# EEZ_DIB_DCP405_r3B3a.net
KiCad netlist of a schematic drawn in EAGLE
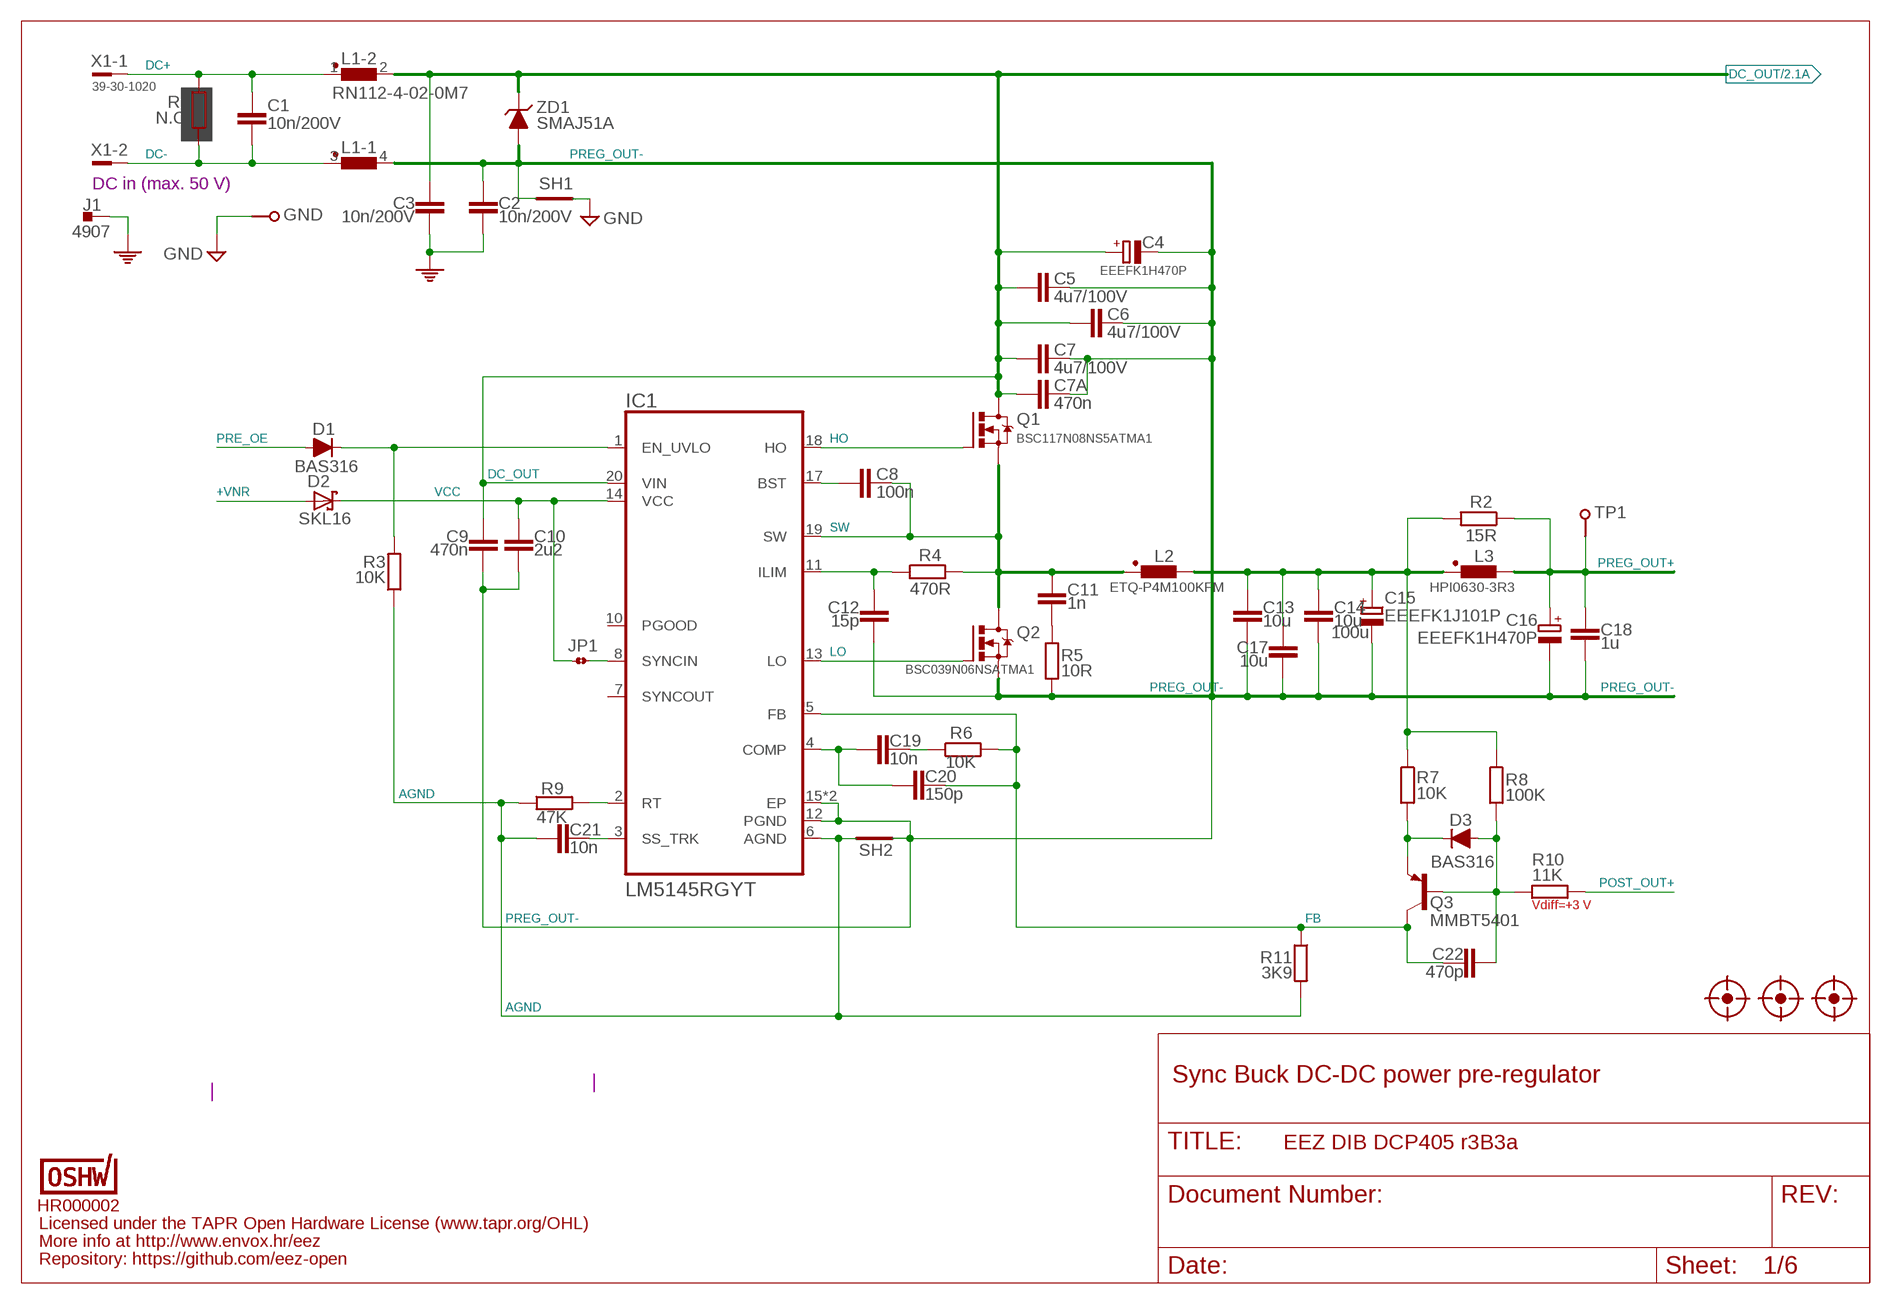
[diagram p0: schematic, sheet 1]
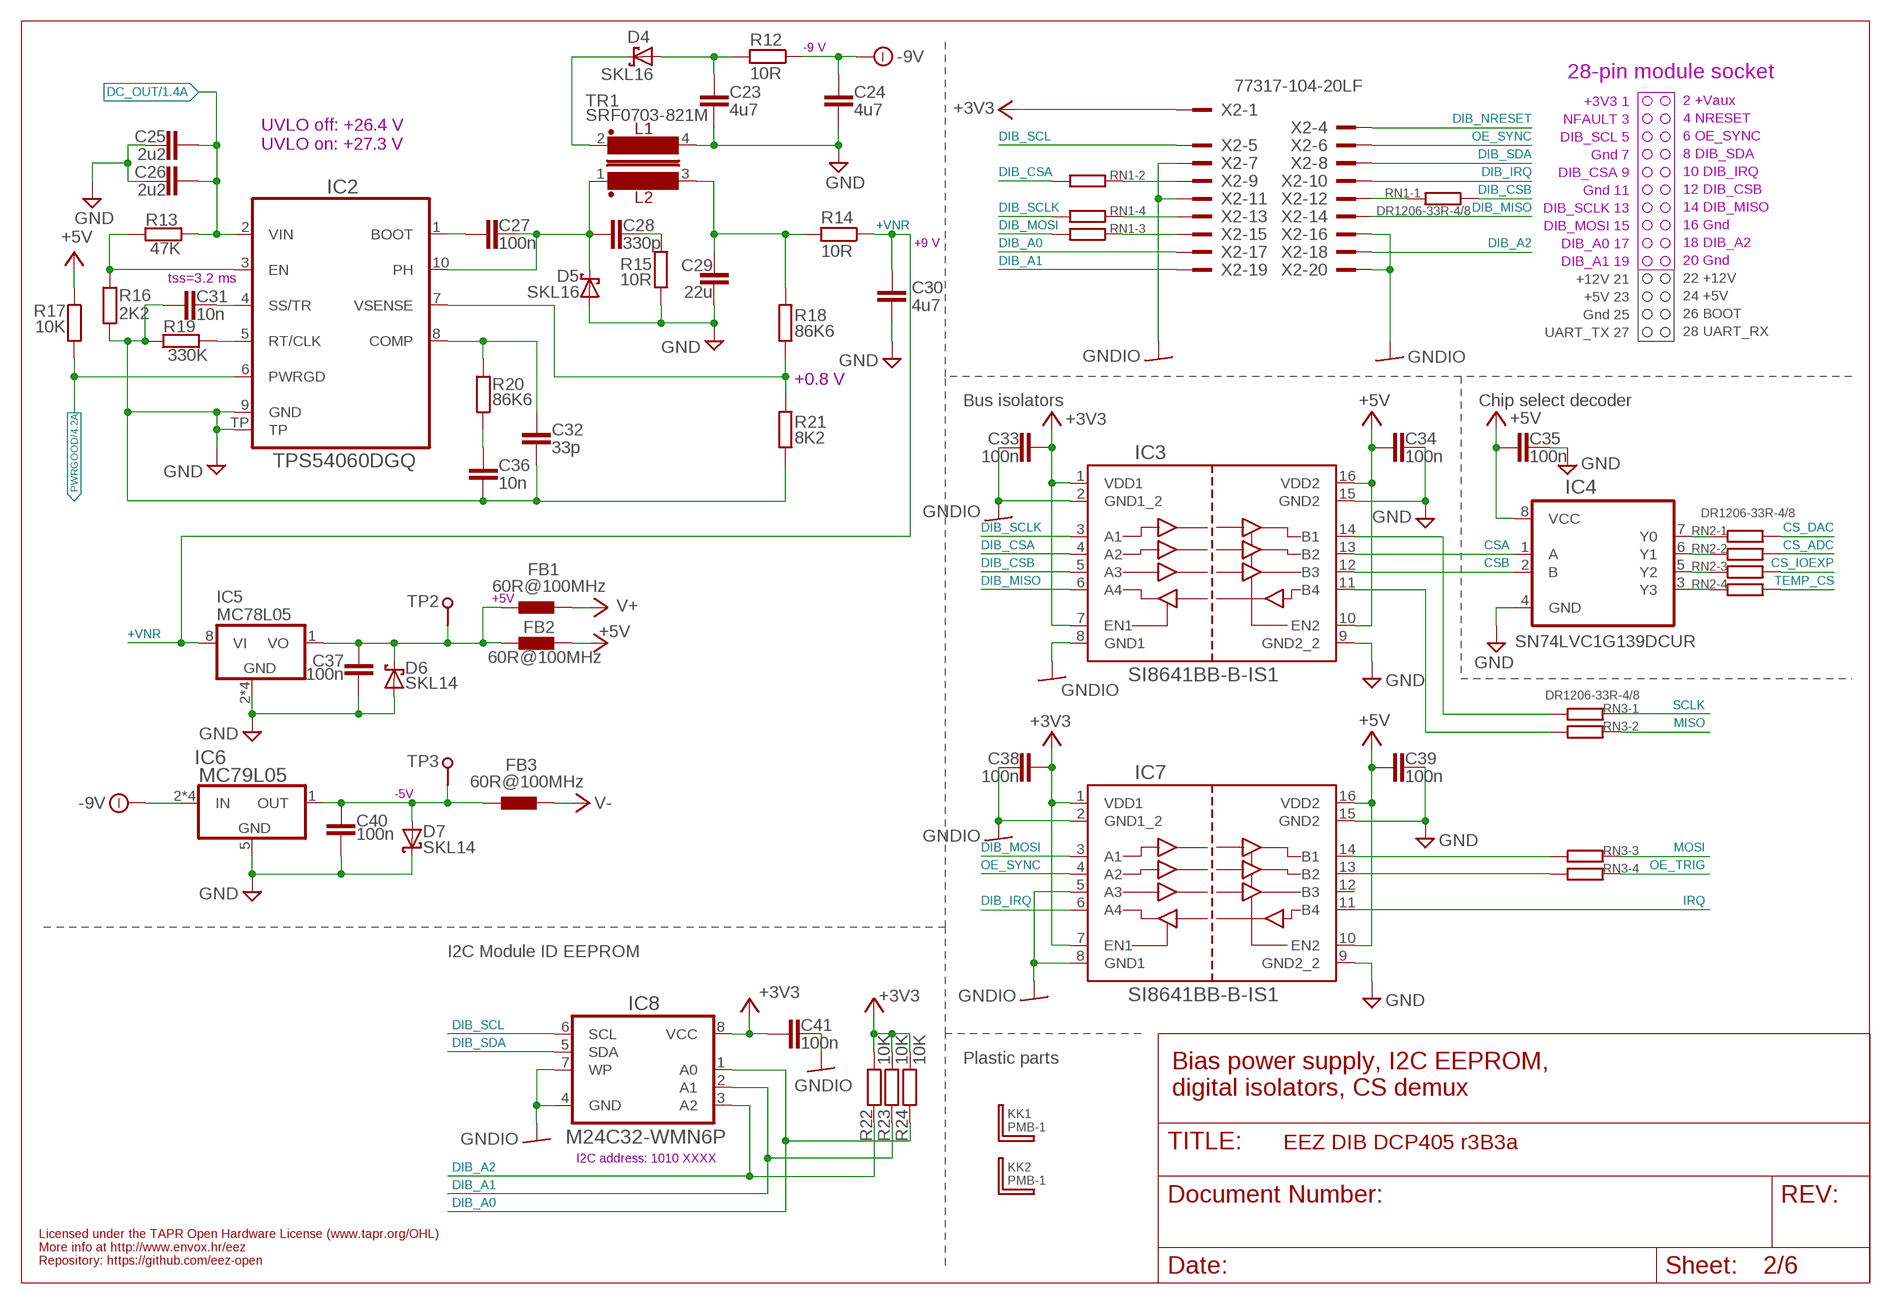
[diagram p1: schematic, sheet 2]
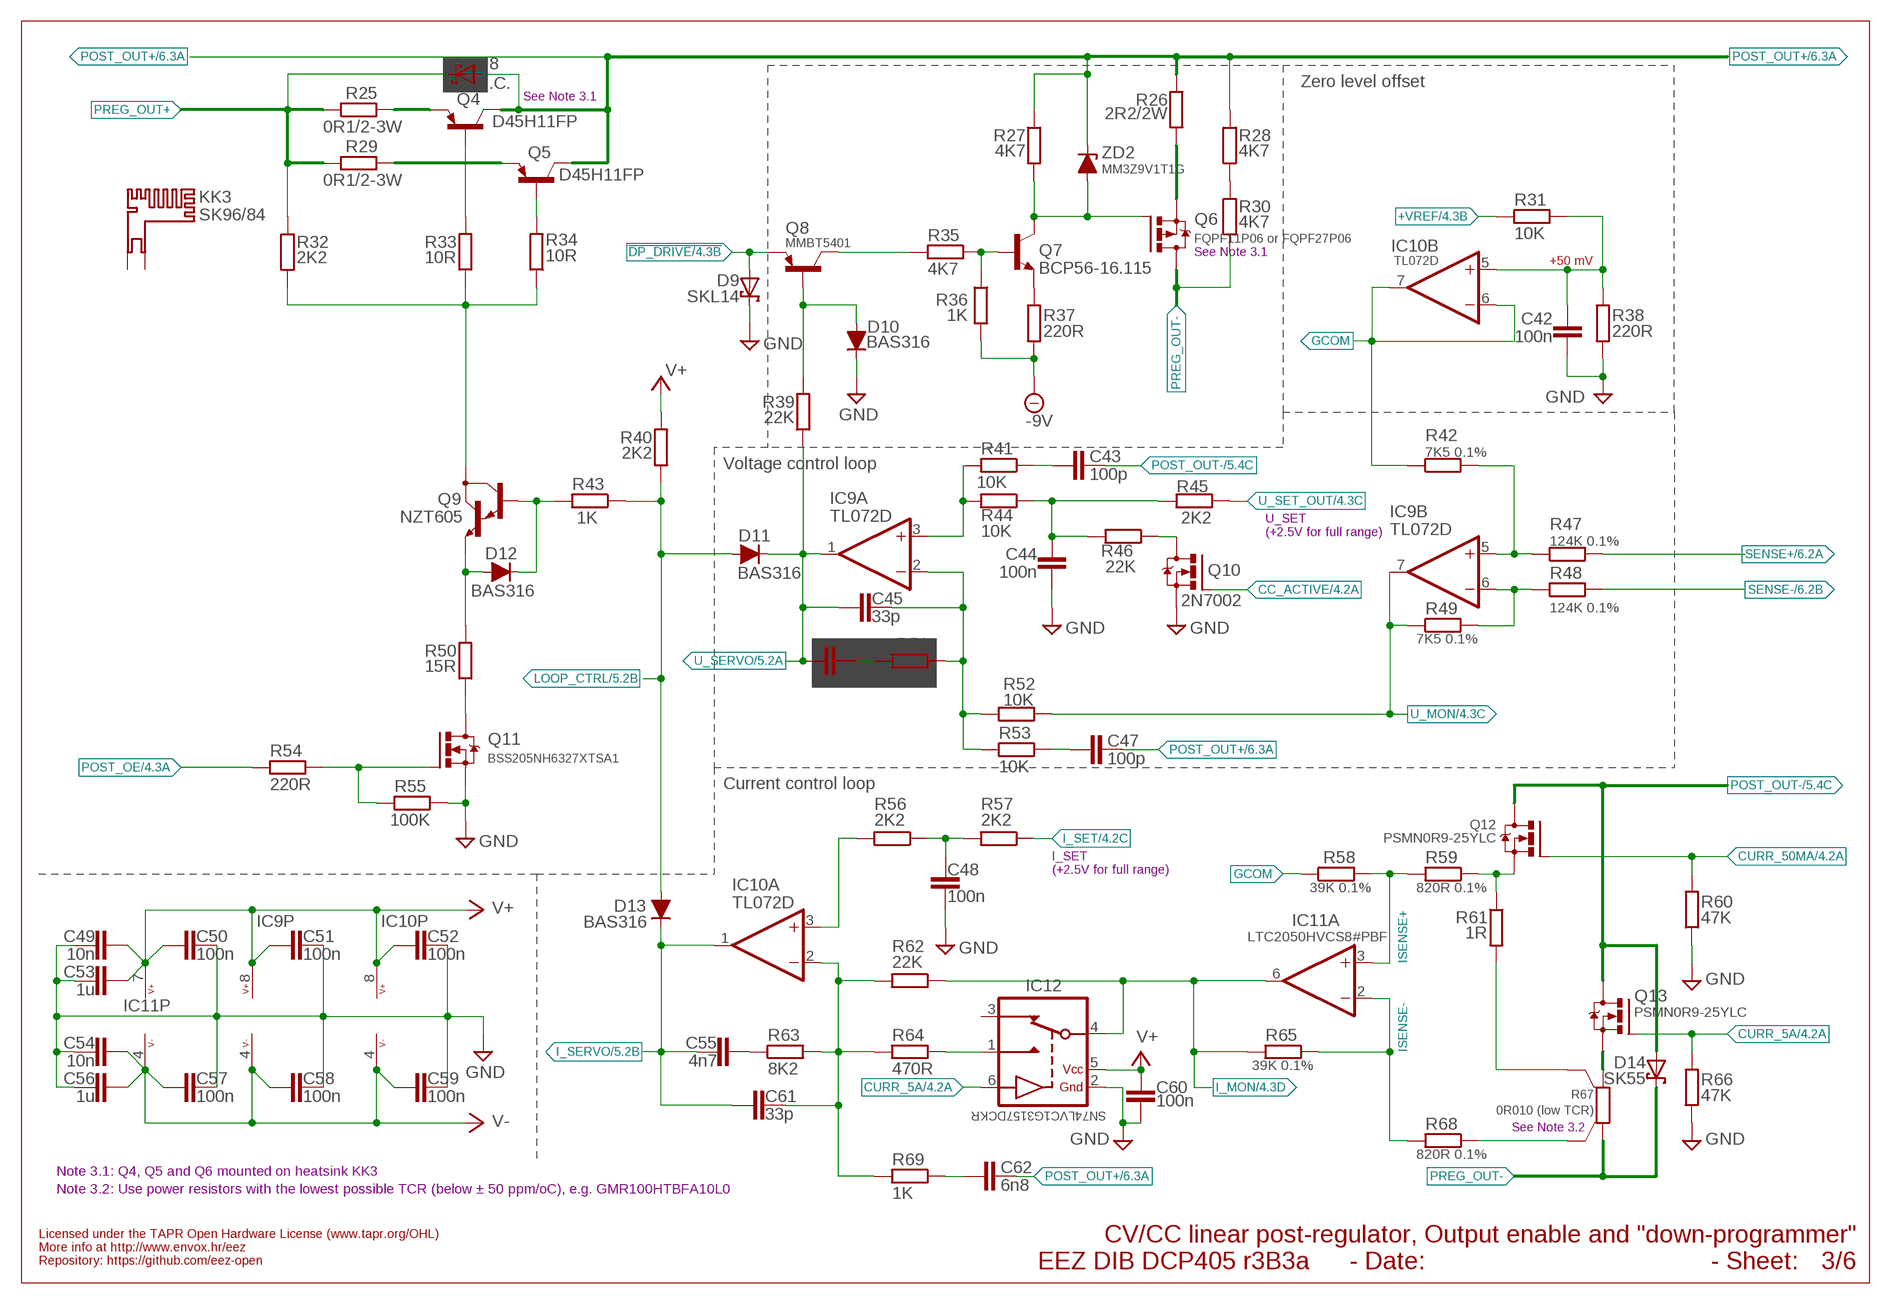
[diagram p2: schematic, sheet 3]
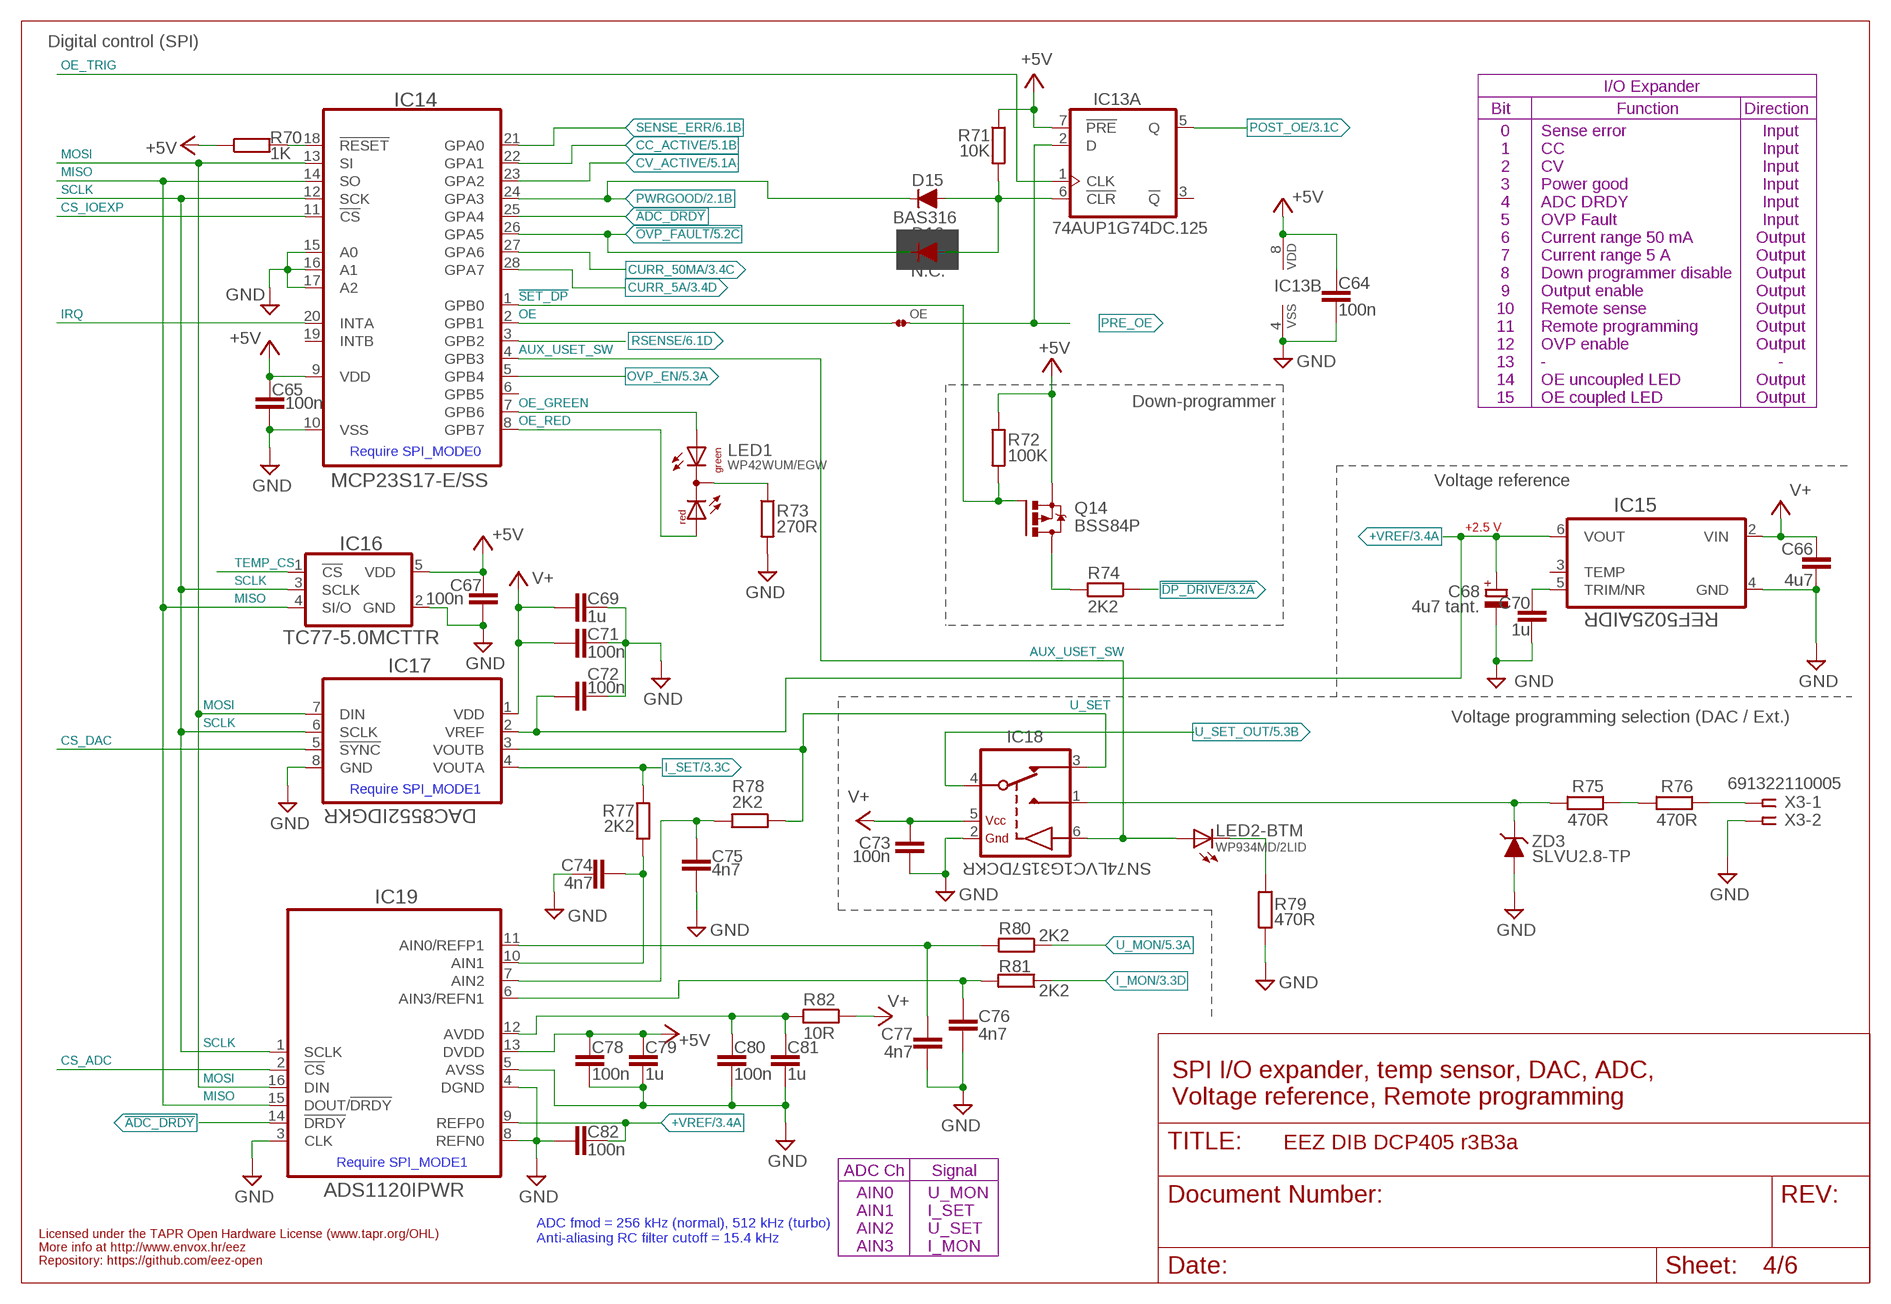
[diagram p3: schematic, sheet 4]
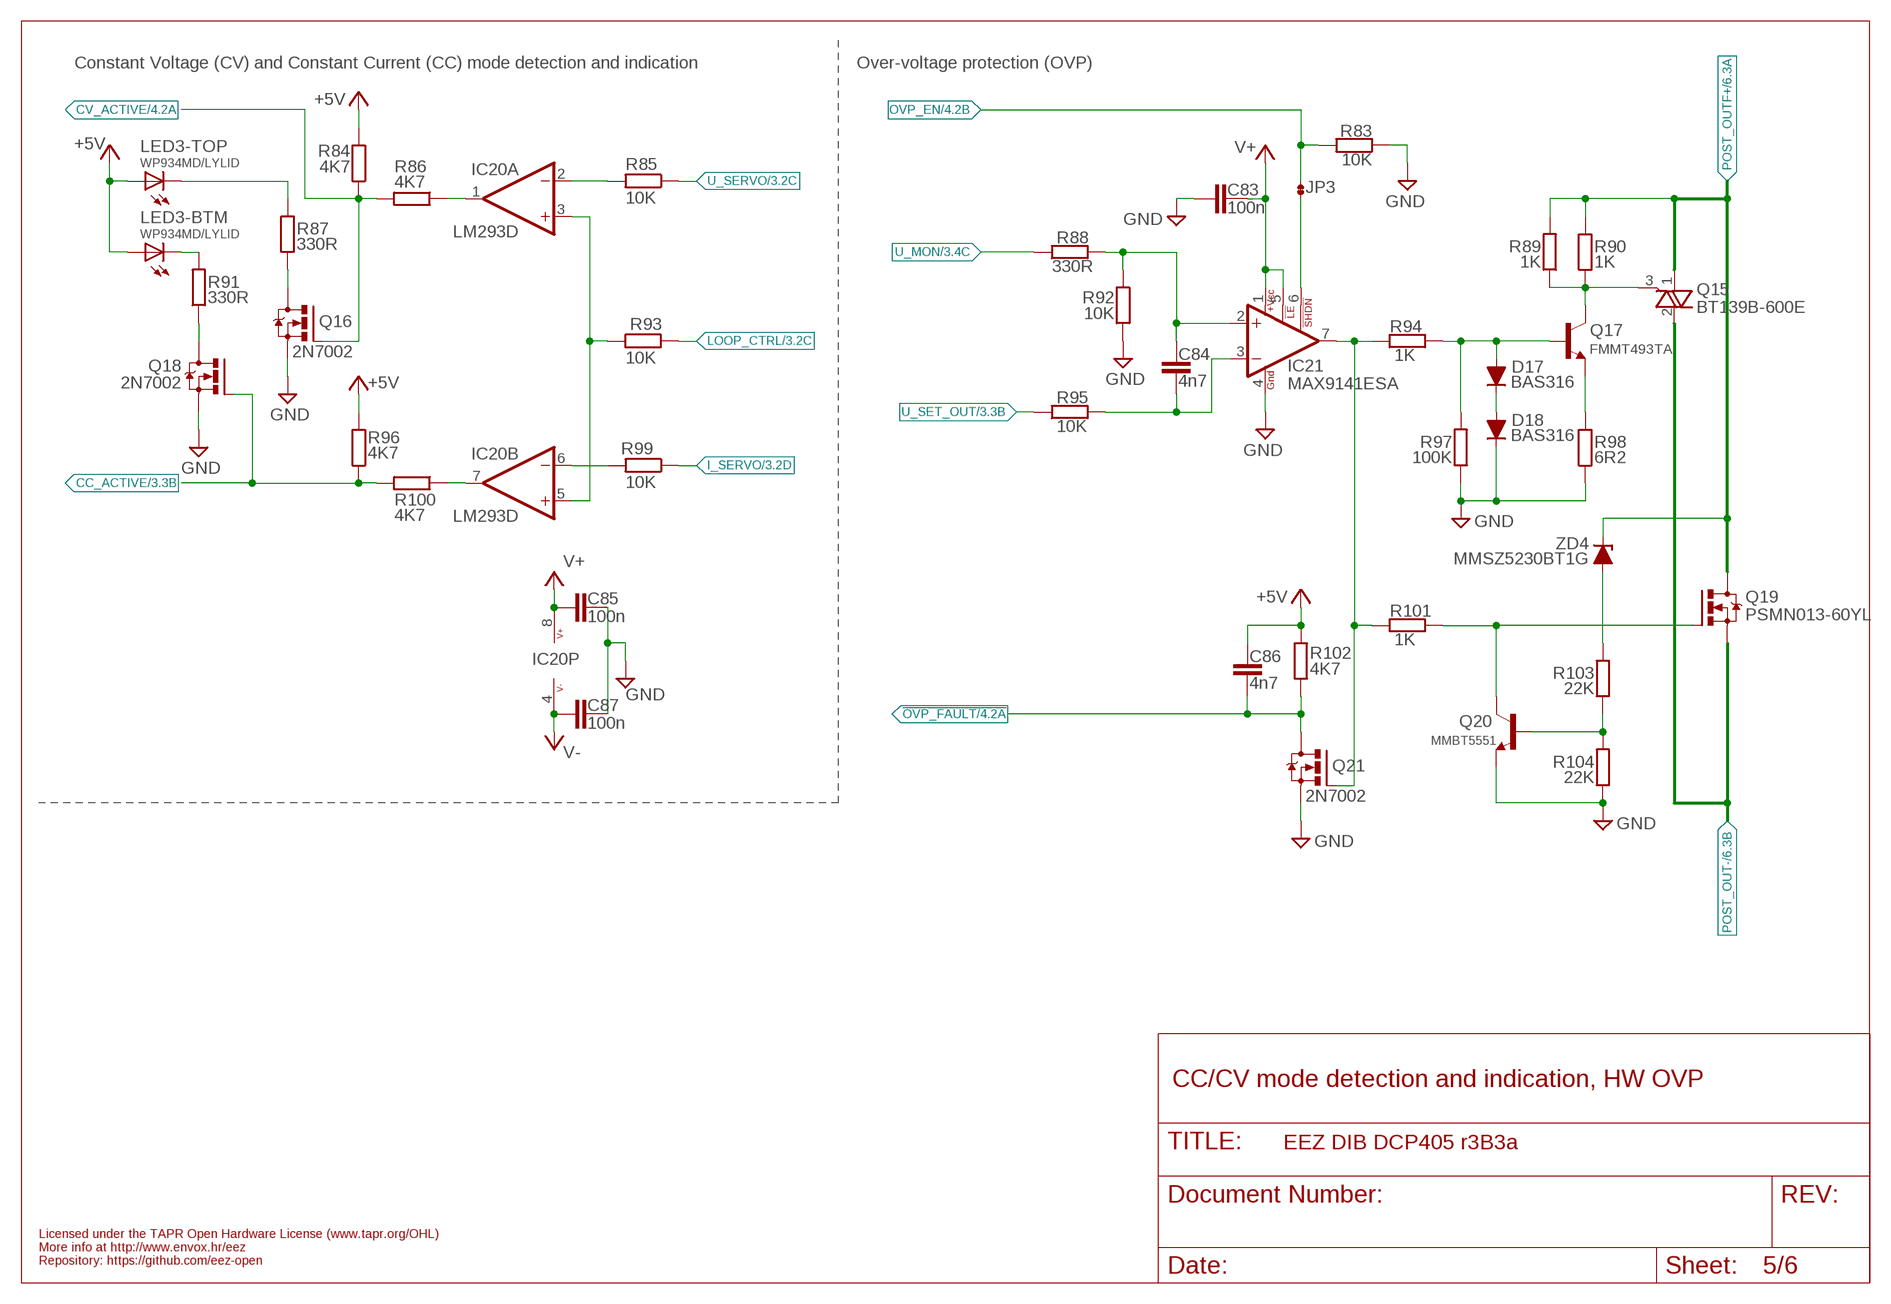
[diagram p4: schematic, sheet 5]
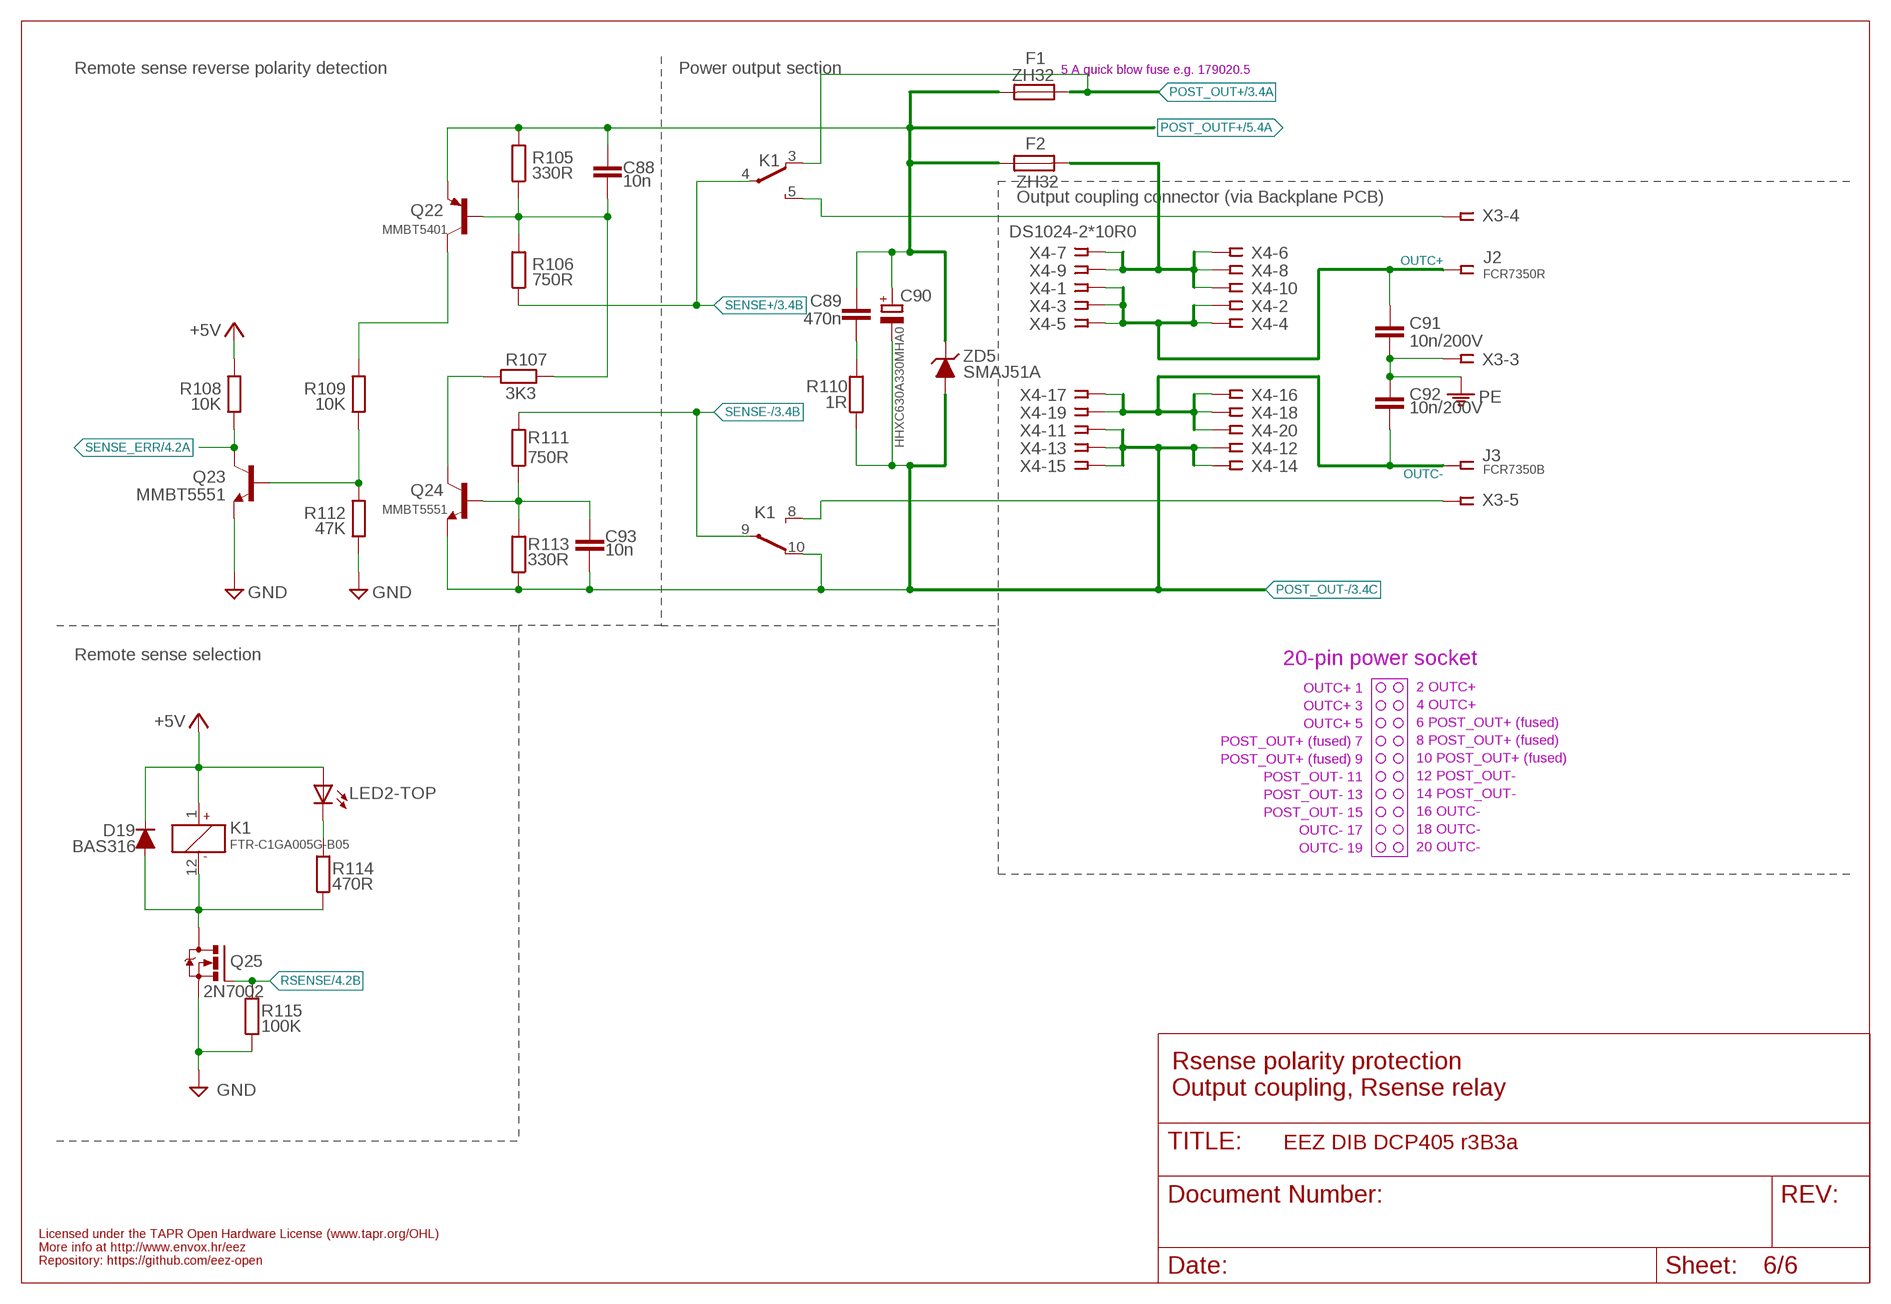
[diagram p5: schematic, sheet 6]

(export (version "E")
  (design (tool "Eeschema 10.0.6"))
  (components
    (comp (ref "C23")
      (value "4u7")
      (footprint "eagle-import:C1206")
      (libsource (lib "eagle-import") (part "C-EUC1206"))
    )
    (comp (ref "C24")
      (value "4u7")
      (footprint "eagle-import:C1206")
      (libsource (lib "eagle-import") (part "C-EUC1206"))
    )
    (comp (ref "C25")
      (value "2u2")
      (footprint "eagle-import:C1206")
      (libsource (lib "eagle-import") (part "C-EUC1206"))
    )
    (comp (ref "C26")
      (value "2u2")
      (footprint "eagle-import:C1206")
      (libsource (lib "eagle-import") (part "C-EUC1206"))
    )
    (comp (ref "C27")
      (value "100n")
      (footprint "eagle-import:C0603")
      (libsource (lib "eagle-import") (part "C-EUC0603"))
    )
    (comp (ref "C28")
      (value "330p")
      (footprint "eagle-import:C0805")
      (libsource (lib "eagle-import") (part "C-EUC0805"))
    )
    (comp (ref "C29")
      (value "22u")
      (footprint "eagle-import:C1210")
      (libsource (lib "eagle-import") (part "C-EUC1210"))
    )
    (comp (ref "C30")
      (value "4u7")
      (footprint "eagle-import:C1206")
      (libsource (lib "eagle-import") (part "C-EUC1206"))
    )
    (comp (ref "C31")
      (value "10n")
      (footprint "eagle-import:C0805")
      (libsource (lib "eagle-import") (part "C-EUC0805"))
    )
    (comp (ref "C32")
      (value "33p")
      (footprint "eagle-import:C0805")
      (libsource (lib "eagle-import") (part "C-EUC0805"))
    )
    (comp (ref "C33")
      (value "100n")
      (footprint "eagle-import:C0603")
      (libsource (lib "eagle-import") (part "C-EUC0603"))
    )
    (comp (ref "C34")
      (value "100n")
      (footprint "eagle-import:C0603")
      (libsource (lib "eagle-import") (part "C-EUC0603"))
    )
    (comp (ref "C35")
      (value "100n")
      (footprint "eagle-import:C0603")
      (libsource (lib "eagle-import") (part "C-EUC0603"))
    )
    (comp (ref "C36")
      (value "10n")
      (footprint "eagle-import:C0805")
      (libsource (lib "eagle-import") (part "C-EUC0805"))
    )
    (comp (ref "C37")
      (value "100n")
      (footprint "eagle-import:C0603")
      (libsource (lib "eagle-import") (part "C-EUC0603"))
    )
    (comp (ref "C38")
      (value "100n")
      (footprint "eagle-import:C0603")
      (libsource (lib "eagle-import") (part "C-EUC0603"))
    )
    (comp (ref "C39")
      (value "100n")
      (footprint "eagle-import:C0603")
      (libsource (lib "eagle-import") (part "C-EUC0603"))
    )
    (comp (ref "C40")
      (value "100n")
      (footprint "eagle-import:C0603")
      (libsource (lib "eagle-import") (part "C-EUC0603"))
    )
    (comp (ref "C41")
      (value "100n")
      (footprint "eagle-import:C0603")
      (libsource (lib "eagle-import") (part "C-EUC0603"))
    )
    (comp (ref "D4")
      (value "SKL16")
      (footprint "eagle-import:SOD123")
      (libsource (lib "eagle-import") (part "SCHOTTKYSOD123"))
    )
    (comp (ref "D5")
      (value "SKL16")
      (footprint "eagle-import:SOD123")
      (libsource (lib "eagle-import") (part "SCHOTTKYSOD123"))
    )
    (comp (ref "D6")
      (value "SKL14")
      (footprint "eagle-import:SOD123")
      (libsource (lib "eagle-import") (part "SCHOTTKYSOD123"))
    )
    (comp (ref "D7")
      (value "SKL14")
      (footprint "eagle-import:SOD123")
      (libsource (lib "eagle-import") (part "SCHOTTKYSOD123"))
    )
    (comp (ref "FB1")
      (value "60R@100MHz")
      (footprint "eagle-import:BEAD0603")
      (libsource (lib "eagle-import") (part "FERRITE_BEAD0603"))
    )
    (comp (ref "FB2")
      (value "60R@100MHz")
      (footprint "eagle-import:BEAD0603")
      (libsource (lib "eagle-import") (part "FERRITE_BEAD0603"))
    )
    (comp (ref "FB3")
      (value "60R@100MHz")
      (footprint "eagle-import:BEAD0603")
      (libsource (lib "eagle-import") (part "FERRITE_BEAD0603"))
    )
    (comp (ref "IC2")
      (value "TPS54060DGQ")
      (footprint "eagle-import:SOP50P490X110-11N")
      (fields (field (name "MPN") "TPS54060ADGQ"))
      (libsource (lib "eagle-import") (part "TPS54060DGQ"))
    )
    (comp (ref "IC3")
      (value "SI8641BB-B-IS1")
      (footprint "eagle-import:SOIC-16")
      (libsource (lib "eagle-import") (part "SI8641NSOIC-16"))
    )
    (comp (ref "IC4")
      (value "SN74LVC1G139DCUR")
      (footprint "eagle-import:DCU8")
      (libsource (lib "eagle-import") (part "SN74LVC1G139-VSSOP"))
    )
    (comp (ref "IC5")
      (value "MC78L05")
      (footprint "eagle-import:SOIC127P600X173-8N")
      (libsource (lib "eagle-import") (part "MC78LXXSOIC8"))
    )
    (comp (ref "IC6")
      (value "MC79L05")
      (footprint "eagle-import:SOIC127P600X173-8N")
      (libsource (lib "eagle-import") (part "MC79LXXSOIC"))
    )
    (comp (ref "IC7")
      (value "SI8641BB-B-IS1")
      (footprint "eagle-import:SOIC-16")
      (libsource (lib "eagle-import") (part "SI8641NSOIC-16"))
    )
    (comp (ref "IC8")
      (value "M24C32-WMN6P")
      (footprint "eagle-import:SOIC127P600X173-8N")
      (libsource (lib "eagle-import") (part "AT24CXXSOIC8"))
    )
    (comp (ref "KK1")
      (value "PMB-1")
      (footprint "eagle-import:PCB-MB")
      (libsource (lib "eagle-import") (part "PCB-MB"))
    )
    (comp (ref "KK2")
      (value "PMB-1")
      (footprint "eagle-import:PCB-MB")
      (libsource (lib "eagle-import") (part "PCB-MB"))
    )
    (comp (ref "R12")
      (value "10R")
      (footprint "eagle-import:R1206")
      (libsource (lib "eagle-import") (part "R-EU_R1206"))
    )
    (comp (ref "R13")
      (value "47K")
      (footprint "eagle-import:R0805")
      (libsource (lib "eagle-import") (part "R-EU_R0805"))
    )
    (comp (ref "R14")
      (value "10R")
      (footprint "eagle-import:R1206")
      (libsource (lib "eagle-import") (part "R-EU_R1206"))
    )
    (comp (ref "R15")
      (value "10R")
      (footprint "eagle-import:R1206")
      (libsource (lib "eagle-import") (part "R-EU_R1206"))
    )
    (comp (ref "R16")
      (value "2K2")
      (footprint "eagle-import:R0805")
      (libsource (lib "eagle-import") (part "R-EU_R0805"))
    )
    (comp (ref "R17")
      (value "10K")
      (footprint "eagle-import:R0805")
      (libsource (lib "eagle-import") (part "R-EU_R0805"))
    )
    (comp (ref "R18")
      (value "86K6")
      (footprint "eagle-import:R0805")
      (libsource (lib "eagle-import") (part "R-EU_R0805"))
    )
    (comp (ref "R19")
      (value "330K")
      (footprint "eagle-import:R0805")
      (libsource (lib "eagle-import") (part "R-EU_R0805"))
    )
    (comp (ref "R20")
      (value "86K6")
      (footprint "eagle-import:R0805")
      (libsource (lib "eagle-import") (part "R-EU_R0805"))
    )
    (comp (ref "R21")
      (value "8K2")
      (footprint "eagle-import:R0805")
      (libsource (lib "eagle-import") (part "R-EU_R0805"))
    )
    (comp (ref "R22")
      (value "10K")
      (footprint "eagle-import:R0805")
      (libsource (lib "eagle-import") (part "R-EU_R0805"))
    )
    (comp (ref "R23")
      (value "10K")
      (footprint "eagle-import:R0805")
      (libsource (lib "eagle-import") (part "R-EU_R0805"))
    )
    (comp (ref "R24")
      (value "10K")
      (footprint "eagle-import:R0805")
      (libsource (lib "eagle-import") (part "R-EU_R0805"))
    )
    (comp (ref "RN1")
      (value "DR1206-33R-4/8")
      (footprint "eagle-import:CAY16")
      (libsource (lib "eagle-import") (part "R_ARRAY4"))
    )
    (comp (ref "RN2")
      (value "DR1206-33R-4/8")
      (footprint "eagle-import:CAY16")
      (libsource (lib "eagle-import") (part "R_ARRAY4"))
    )
    (comp (ref "RN3")
      (value "DR1206-33R-4/8")
      (footprint "eagle-import:CAY16")
      (libsource (lib "eagle-import") (part "R_ARRAY4"))
    )
    (comp (ref "TP2")
      (value "TEST-PIN_0.9MM")
      (footprint "eagle-import:TEST-PIN_0.9MM")
      (libsource (lib "eagle-import") (part "TEST-PIN_0.9MM"))
    )
    (comp (ref "TP3")
      (value "TEST-PIN_0.9MM")
      (footprint "eagle-import:TEST-PIN_0.9MM")
      (libsource (lib "eagle-import") (part "TEST-PIN_0.9MM"))
    )
    (comp (ref "TR1")
      (value "SRF0703-821M")
      (footprint "eagle-import:SRF0703")
      (libsource (lib "eagle-import") (part "BOURNS_SRF0703INV"))
    )
    (comp (ref "X2")
      (value "77317-104-20LF")
      (footprint "eagle-import:77317-104-20LF")
      (libsource (lib "eagle-import") (part "77317-104-20LF"))
    )
    (comp (ref "C83")
      (value "100n")
      (footprint "eagle-import:C0603")
      (libsource (lib "eagle-import") (part "C-EUC0603"))
    )
    (comp (ref "C84")
      (value "4n7")
      (footprint "eagle-import:C0805")
      (libsource (lib "eagle-import") (part "C-EUC0805"))
    )
    (comp (ref "C85")
      (value "100n")
      (footprint "eagle-import:C0603")
      (libsource (lib "eagle-import") (part "C-EUC0603"))
    )
    (comp (ref "C86")
      (value "4n7")
      (footprint "eagle-import:C0805")
      (libsource (lib "eagle-import") (part "C-EUC0805"))
    )
    (comp (ref "C87")
      (value "100n")
      (footprint "eagle-import:C0603")
      (libsource (lib "eagle-import") (part "C-EUC0603"))
    )
    (comp (ref "D17")
      (value "BAS316")
      (footprint "eagle-import:SOD323-R")
      (libsource (lib "eagle-import") (part "DIODESOD323R"))
    )
    (comp (ref "D18")
      (value "BAS316")
      (footprint "eagle-import:SOD323-R")
      (libsource (lib "eagle-import") (part "DIODESOD323R"))
    )
    (comp (ref "IC20")
      (value "LM293D")
      (footprint "eagle-import:SOIC127P600X173-8N")
      (libsource (lib "eagle-import") (part "LM293D"))
    )
    (comp (ref "IC21")
      (value "MAX9141ESA")
      (footprint "eagle-import:SOIC127P600X173-8N")
      (libsource (lib "eagle-import") (part "MAX9141ESA"))
    )
    (comp (ref "JP3")
      (value "JP2-NOCUT-0805")
      (footprint "eagle-import:JP2-0805-NOCUT")
      (libsource (lib "eagle-import") (part "JP2-NOCUT-0805"))
    )
    (comp (ref "LED3")
      (value "WP934MD/LYLID")
      (footprint "eagle-import:WP934MD")
      (libsource (lib "eagle-import") (part "WP934MD/LYLID"))
    )
    (comp (ref "Q15")
      (value "BT139B-600E")
      (footprint "eagle-import:D2PAK")
      (libsource (lib "eagle-import") (part "BT139"))
    )
    (comp (ref "Q16")
      (value "2N7002")
      (footprint "eagle-import:SOT103P240X110-3N")
      (fields (field (name "MPN") "2N7002-7-F"))
      (libsource (lib "eagle-import") (part "2N7002"))
    )
    (comp (ref "Q17")
      (value "FMMT493TA")
      (footprint "eagle-import:SOT23-BEC")
      (libsource (lib "eagle-import") (part "-NPN-SOT23-BECMMBT5551LT1"))
    )
    (comp (ref "Q18")
      (value "2N7002")
      (footprint "eagle-import:SOT103P240X110-3N")
      (fields (field (name "MPN") "2N7002-7-F"))
      (libsource (lib "eagle-import") (part "2N7002"))
    )
    (comp (ref "Q19")
      (value "PSMN013-60YL")
      (footprint "eagle-import:SOT669")
      (libsource (lib "eagle-import") (part "N-MOSFETLFPAK"))
    )
    (comp (ref "Q20")
      (value "MMBT5551")
      (footprint "eagle-import:SOT23-BEC")
      (libsource (lib "eagle-import") (part "-NPN-SOT23-BECMMBT5551LT1"))
    )
    (comp (ref "Q21")
      (value "2N7002")
      (footprint "eagle-import:SOT103P240X110-3N")
      (fields (field (name "MPN") "2N7002-7-F"))
      (libsource (lib "eagle-import") (part "2N7002"))
    )
    (comp (ref "R83")
      (value "10K")
      (footprint "eagle-import:R0805")
      (libsource (lib "eagle-import") (part "R-EU_R0805"))
    )
    (comp (ref "R84")
      (value "4K7")
      (footprint "eagle-import:R0805")
      (libsource (lib "eagle-import") (part "R-EU_R0805"))
    )
    (comp (ref "R85")
      (value "10K")
      (footprint "eagle-import:R0805")
      (libsource (lib "eagle-import") (part "R-EU_R0805"))
    )
    (comp (ref "R86")
      (value "4K7")
      (footprint "eagle-import:R0805")
      (libsource (lib "eagle-import") (part "R-EU_R0805"))
    )
    (comp (ref "R87")
      (value "330R")
      (footprint "eagle-import:R0805")
      (libsource (lib "eagle-import") (part "R-EU_R0805"))
    )
    (comp (ref "R88")
      (value "330R")
      (footprint "eagle-import:R0805")
      (libsource (lib "eagle-import") (part "R-EU_R0805"))
    )
    (comp (ref "R89")
      (value "1K")
      (footprint "eagle-import:R0805")
      (libsource (lib "eagle-import") (part "R-EU_R0805"))
    )
    (comp (ref "R90")
      (value "1K")
      (footprint "eagle-import:R0805")
      (libsource (lib "eagle-import") (part "R-EU_R0805"))
    )
    (comp (ref "R91")
      (value "330R")
      (footprint "eagle-import:R0805")
      (libsource (lib "eagle-import") (part "R-EU_R0805"))
    )
    (comp (ref "R92")
      (value "10K")
      (footprint "eagle-import:R0805")
      (libsource (lib "eagle-import") (part "R-EU_R0805"))
    )
    (comp (ref "R93")
      (value "10K")
      (footprint "eagle-import:R0805")
      (libsource (lib "eagle-import") (part "R-EU_R0805"))
    )
    (comp (ref "R94")
      (value "1K")
      (footprint "eagle-import:R0805")
      (libsource (lib "eagle-import") (part "R-EU_R0805"))
    )
    (comp (ref "R95")
      (value "10K")
      (footprint "eagle-import:R0805")
      (libsource (lib "eagle-import") (part "R-EU_R0805"))
    )
    (comp (ref "R96")
      (value "4K7")
      (footprint "eagle-import:R0805")
      (libsource (lib "eagle-import") (part "R-EU_R0805"))
    )
    (comp (ref "R97")
      (value "100K")
      (footprint "eagle-import:R0805")
      (libsource (lib "eagle-import") (part "R-EU_R0805"))
    )
    (comp (ref "R98")
      (value "6R2")
      (footprint "eagle-import:R0805")
      (libsource (lib "eagle-import") (part "R-EU_R0805"))
    )
    (comp (ref "R99")
      (value "10K")
      (footprint "eagle-import:R0805")
      (libsource (lib "eagle-import") (part "R-EU_R0805"))
    )
    (comp (ref "R100")
      (value "4K7")
      (footprint "eagle-import:R0805")
      (libsource (lib "eagle-import") (part "R-EU_R0805"))
    )
    (comp (ref "R101")
      (value "1K")
      (footprint "eagle-import:R0805")
      (libsource (lib "eagle-import") (part "R-EU_R0805"))
    )
    (comp (ref "R102")
      (value "4K7")
      (footprint "eagle-import:R0805")
      (libsource (lib "eagle-import") (part "R-EU_R0805"))
    )
    (comp (ref "R103")
      (value "22K")
      (footprint "eagle-import:R0805")
      (libsource (lib "eagle-import") (part "R-EU_R0805"))
    )
    (comp (ref "R104")
      (value "22K")
      (footprint "eagle-import:R0805")
      (libsource (lib "eagle-import") (part "R-EU_R0805"))
    )
    (comp (ref "ZD4")
      (value "MMSZ5230BT1G")
      (footprint "eagle-import:SOD123")
      (libsource (lib "eagle-import") (part "ZENER-DIODESOD123"))
    )
    (comp (ref "C1")
      (value "10n/200V")
      (footprint "eagle-import:C1206")
      (libsource (lib "eagle-import") (part "C-EUC1206"))
    )
    (comp (ref "C2")
      (value "10n/200V")
      (footprint "eagle-import:C1206")
      (libsource (lib "eagle-import") (part "C-EUC1206"))
    )
    (comp (ref "C3")
      (value "10n/200V")
      (footprint "eagle-import:C1206")
      (libsource (lib "eagle-import") (part "C-EUC1206"))
    )
    (comp (ref "C4")
      (value "EEEFK1H470P")
      (footprint "eagle-import:CAPAE830X1050N")
      (libsource (lib "eagle-import") (part "ECAPSMD8.3MM/HA0"))
    )
    (comp (ref "C5")
      (value "4u7/100V")
      (footprint "eagle-import:C1210")
      (libsource (lib "eagle-import") (part "C-EUC1210"))
    )
    (comp (ref "C6")
      (value "4u7/100V")
      (footprint "eagle-import:C1210")
      (libsource (lib "eagle-import") (part "C-EUC1210"))
    )
    (comp (ref "C7")
      (value "4u7/100V")
      (footprint "eagle-import:C1210")
      (libsource (lib "eagle-import") (part "C-EUC1210"))
    )
    (comp (ref "C7A")
      (value "470n")
      (footprint "eagle-import:C0805")
      (libsource (lib "eagle-import") (part "C-EUC0805"))
    )
    (comp (ref "C8")
      (value "100n")
      (footprint "eagle-import:C0603")
      (libsource (lib "eagle-import") (part "C-EUC0603"))
    )
    (comp (ref "C9")
      (value "470n")
      (footprint "eagle-import:C0805")
      (libsource (lib "eagle-import") (part "C-EUC0805"))
    )
    (comp (ref "C10")
      (value "2u2")
      (footprint "eagle-import:C1206")
      (libsource (lib "eagle-import") (part "C-EUC1206"))
    )
    (comp (ref "C11")
      (value "1n")
      (footprint "eagle-import:C0805")
      (libsource (lib "eagle-import") (part "C-EUC0805"))
    )
    (comp (ref "C12")
      (value "15p")
      (footprint "eagle-import:C0805")
      (libsource (lib "eagle-import") (part "C-EUC0805"))
    )
    (comp (ref "C13")
      (value "10u")
      (footprint "eagle-import:C1210")
      (libsource (lib "eagle-import") (part "C-EUC1210"))
    )
    (comp (ref "C14")
      (value "10u")
      (footprint "eagle-import:C1210")
      (libsource (lib "eagle-import") (part "C-EUC1210"))
    )
    (comp (ref "C15")
      (value "EEEFK1J101P")
      (footprint "eagle-import:CAPAE1030X1050N")
      (libsource (lib "eagle-import") (part "ECAP10X10"))
    )
    (comp (ref "C16")
      (value "EEEFK1H470P")
      (footprint "eagle-import:CAPAE830X1050N")
      (libsource (lib "eagle-import") (part "ECAPSMD8.3MM/HA0"))
    )
    (comp (ref "C17")
      (value "10u")
      (footprint "eagle-import:C1210")
      (libsource (lib "eagle-import") (part "C-EUC1210"))
    )
    (comp (ref "C18")
      (value "1u")
      (footprint "eagle-import:C0805")
      (libsource (lib "eagle-import") (part "C-EUC0805"))
    )
    (comp (ref "C19")
      (value "10n")
      (footprint "eagle-import:C0805")
      (libsource (lib "eagle-import") (part "C-EUC0805"))
    )
    (comp (ref "C20")
      (value "150p")
      (footprint "eagle-import:C0805")
      (libsource (lib "eagle-import") (part "C-EUC0805"))
    )
    (comp (ref "C21")
      (value "10n")
      (footprint "eagle-import:C0805")
      (libsource (lib "eagle-import") (part "C-EUC0805"))
    )
    (comp (ref "C22")
      (value "470p")
      (footprint "eagle-import:C0805")
      (libsource (lib "eagle-import") (part "C-EUC0805"))
    )
    (comp (ref "D1")
      (value "BAS316")
      (footprint "eagle-import:SOD323-R")
      (libsource (lib "eagle-import") (part "DIODESOD323R"))
    )
    (comp (ref "D2")
      (value "SKL16")
      (footprint "eagle-import:SOD123")
      (libsource (lib "eagle-import") (part "SCHOTTKYSOD123"))
    )
    (comp (ref "D3")
      (value "BAS316")
      (footprint "eagle-import:SOD323-R")
      (libsource (lib "eagle-import") (part "DIODESOD323R"))
    )
    (comp (ref "FM1")
      (value "FIDUCIAL_2")
      (footprint "eagle-import:FIDUCIAL_DUAL")
      (libsource (lib "eagle-import") (part "FIDUCIAL_2"))
    )
    (comp (ref "FM2")
      (value "FIDUCIAL_2")
      (footprint "eagle-import:FIDUCIAL_DUAL")
      (libsource (lib "eagle-import") (part "FIDUCIAL_2"))
    )
    (comp (ref "FM3")
      (value "FIDUCIAL_2")
      (footprint "eagle-import:FIDUCIAL_DUAL")
      (libsource (lib "eagle-import") (part "FIDUCIAL_2"))
    )
    (comp (ref "GND")
      (value "PCB_TEST_TABSHIELD")
      (footprint "eagle-import:PCB_SHIELD_TAB")
      (libsource (lib "eagle-import") (part "PCB_TEST_TABSHIELD"))
    )
    (comp (ref "IC1")
      (value "LM5145RGYT")
      (footprint "eagle-import:RGY0020B")
      (libsource (lib "eagle-import") (part "LM5145RGYR"))
    )
    (comp (ref "J1")
      (value "4907")
      (footprint "eagle-import:PCB_TAB-4907")
      (libsource (lib "eagle-import") (part "PCB_TAB-4907"))
    )
    (comp (ref "JP1")
      (value "JP2-CUT-0805")
      (footprint "eagle-import:R_0805")
      (libsource (lib "eagle-import") (part "JP2-CUT-0805"))
    )
    (comp (ref "L1")
      (value "RN112-4-02-0M7")
      (footprint "eagle-import:RN112")
      (libsource (lib "eagle-import") (part "RN112"))
    )
    (comp (ref "L2")
      (value "ETQ-P4M100KFM")
      (footprint "eagle-import:PANASONIC_ETQ-P4_KFM")
      (libsource (lib "eagle-import") (part "PANASONIC_ETQ-P4_KFM"))
    )
    (comp (ref "L3")
      (value "HPI0630-3R3")
      (footprint "eagle-import:COILCRAFT_HPI0630")
      (libsource (lib "eagle-import") (part "COILCRAFT_HPI0630"))
    )
    (comp (ref "OSHWA")
      (value "HR000002")
      (footprint "eagle-import:CERT-SMALL-SILK")
      (libsource (lib "eagle-import") (part "OSHWA-CERT-SMALL"))
    )
    (comp (ref "Q1")
      (value "BSC117N08NS5ATMA1")
      (footprint "eagle-import:TDSON-8")
      (libsource (lib "eagle-import") (part "N-MOSFETTDSON-8"))
    )
    (comp (ref "Q2")
      (value "BSC039N06NSATMA1")
      (footprint "eagle-import:TDSON-8")
      (libsource (lib "eagle-import") (part "N-MOSFETTDSON-8"))
    )
    (comp (ref "Q3")
      (value "MMBT5401")
      (footprint "eagle-import:SOT23-BEC")
      (libsource (lib "eagle-import") (part "-PNP-SOT23-BECBC857B"))
    )
    (comp (ref "R1")
      (value "N.C.")
      (footprint "eagle-import:R2512")
      (libsource (lib "eagle-import") (part "R-EU_R2512"))
    )
    (comp (ref "R2")
      (value "15R")
      (footprint "eagle-import:R2010")
      (libsource (lib "eagle-import") (part "R-EU_R2010"))
    )
    (comp (ref "R3")
      (value "10K")
      (footprint "eagle-import:R0805")
      (libsource (lib "eagle-import") (part "R-EU_R0805"))
    )
    (comp (ref "R4")
      (value "470R")
      (footprint "eagle-import:R0805")
      (libsource (lib "eagle-import") (part "R-EU_R0805"))
    )
    (comp (ref "R5")
      (value "10R")
      (footprint "eagle-import:R1206")
      (libsource (lib "eagle-import") (part "R-EU_R1206"))
    )
    (comp (ref "R6")
      (value "10K")
      (footprint "eagle-import:R0805")
      (libsource (lib "eagle-import") (part "R-EU_R0805"))
    )
    (comp (ref "R7")
      (value "10K")
      (footprint "eagle-import:R0805")
      (libsource (lib "eagle-import") (part "R-EU_R0805"))
    )
    (comp (ref "R8")
      (value "100K")
      (footprint "eagle-import:R0805")
      (libsource (lib "eagle-import") (part "R-EU_R0805"))
    )
    (comp (ref "R9")
      (value "47K")
      (footprint "eagle-import:R0805")
      (libsource (lib "eagle-import") (part "R-EU_R0805"))
    )
    (comp (ref "R10")
      (value "11K")
      (footprint "eagle-import:R0805")
      (libsource (lib "eagle-import") (part "R-EU_R0805"))
    )
    (comp (ref "R11")
      (value "3K9")
      (footprint "eagle-import:R0805")
      (libsource (lib "eagle-import") (part "R-EU_R0805"))
    )
    (comp (ref "SH1")
      (value "SHORTNOHOLE")
      (footprint "eagle-import:SHORT_NOHOLE")
      (libsource (lib "eagle-import") (part "SHORTNOHOLE"))
    )
    (comp (ref "SH2")
      (value "SHORTNOHOLE")
      (footprint "eagle-import:SHORT_NOHOLE")
      (libsource (lib "eagle-import") (part "SHORTNOHOLE"))
    )
    (comp (ref "TP1")
      (value "TEST-PIN_0.9MM")
      (footprint "eagle-import:TEST-PIN_0.9MM")
      (libsource (lib "eagle-import") (part "TEST-PIN_0.9MM"))
    )
    (comp (ref "X1")
      (value "39-30-1020")
      (footprint "eagle-import:MINIFIT_39301020")
      (libsource (lib "eagle-import") (part "MINIFIT_39301020"))
    )
    (comp (ref "ZD1")
      (value "SMAJ51A")
      (footprint "eagle-import:DO214AA")
      (libsource (lib "eagle-import") (part "P6SMB68A"))
    )
    (comp (ref "C42")
      (value "100n")
      (footprint "eagle-import:C0603")
      (libsource (lib "eagle-import") (part "C-EUC0603"))
    )
    (comp (ref "C43")
      (value "100p")
      (footprint "eagle-import:C0805")
      (libsource (lib "eagle-import") (part "C-EUC0805"))
    )
    (comp (ref "C44")
      (value "100n")
      (footprint "eagle-import:C0603")
      (libsource (lib "eagle-import") (part "C-EUC0603"))
    )
    (comp (ref "C45")
      (value "33p")
      (footprint "eagle-import:C0805")
      (libsource (lib "eagle-import") (part "C-EUC0805"))
    )
    (comp (ref "C46")
      (value "N.C.")
      (footprint "eagle-import:C0805")
      (libsource (lib "eagle-import") (part "C-EUC0805"))
    )
    (comp (ref "C47")
      (value "100p")
      (footprint "eagle-import:C0805")
      (libsource (lib "eagle-import") (part "C-EUC0805"))
    )
    (comp (ref "C48")
      (value "100n")
      (footprint "eagle-import:C0603")
      (libsource (lib "eagle-import") (part "C-EUC0603"))
    )
    (comp (ref "C49")
      (value "10n")
      (footprint "eagle-import:C0805")
      (libsource (lib "eagle-import") (part "C-EUC0805"))
    )
    (comp (ref "C50")
      (value "100n")
      (footprint "eagle-import:C0603")
      (libsource (lib "eagle-import") (part "C-EUC0603"))
    )
    (comp (ref "C51")
      (value "100n")
      (footprint "eagle-import:C0603")
      (libsource (lib "eagle-import") (part "C-EUC0603"))
    )
    (comp (ref "C52")
      (value "100n")
      (footprint "eagle-import:C0603")
      (libsource (lib "eagle-import") (part "C-EUC0603"))
    )
    (comp (ref "C53")
      (value "1u")
      (footprint "eagle-import:C0805")
      (libsource (lib "eagle-import") (part "C-EUC0805"))
    )
    (comp (ref "C54")
      (value "10n")
      (footprint "eagle-import:C0805")
      (libsource (lib "eagle-import") (part "C-EUC0805"))
    )
    (comp (ref "C55")
      (value "4n7")
      (footprint "eagle-import:C0805")
      (libsource (lib "eagle-import") (part "C-EUC0805"))
    )
    (comp (ref "C56")
      (value "1u")
      (footprint "eagle-import:C0805")
      (libsource (lib "eagle-import") (part "C-EUC0805"))
    )
    (comp (ref "C57")
      (value "100n")
      (footprint "eagle-import:C0603")
      (libsource (lib "eagle-import") (part "C-EUC0603"))
    )
    (comp (ref "C58")
      (value "100n")
      (footprint "eagle-import:C0603")
      (libsource (lib "eagle-import") (part "C-EUC0603"))
    )
    (comp (ref "C59")
      (value "100n")
      (footprint "eagle-import:C0603")
      (libsource (lib "eagle-import") (part "C-EUC0603"))
    )
    (comp (ref "C60")
      (value "100n")
      (footprint "eagle-import:C0603")
      (libsource (lib "eagle-import") (part "C-EUC0603"))
    )
    (comp (ref "C61")
      (value "33p")
      (footprint "eagle-import:C0805")
      (libsource (lib "eagle-import") (part "C-EUC0805"))
    )
    (comp (ref "C62")
      (value "6n8")
      (footprint "eagle-import:C0805")
      (libsource (lib "eagle-import") (part "C-EUC0805"))
    )
    (comp (ref "D8")
      (value "N.C.")
      (footprint "eagle-import:SOD123")
      (libsource (lib "eagle-import") (part "SCHOTTKYSOD123"))
    )
    (comp (ref "D9")
      (value "SKL14")
      (footprint "eagle-import:SOD123")
      (libsource (lib "eagle-import") (part "SCHOTTKYSOD123"))
    )
    (comp (ref "D10")
      (value "BAS316")
      (footprint "eagle-import:SOD323-R")
      (libsource (lib "eagle-import") (part "DIODESOD323R"))
    )
    (comp (ref "D11")
      (value "BAS316")
      (footprint "eagle-import:SOD323-R")
      (libsource (lib "eagle-import") (part "DIODESOD323R"))
    )
    (comp (ref "D12")
      (value "BAS316")
      (footprint "eagle-import:SOD323-R")
      (libsource (lib "eagle-import") (part "DIODESOD323R"))
    )
    (comp (ref "D13")
      (value "BAS316")
      (footprint "eagle-import:SOD323-R")
      (libsource (lib "eagle-import") (part "DIODESOD323R"))
    )
    (comp (ref "D14")
      (value "SK55")
      (footprint "eagle-import:SMB")
      (libsource (lib "eagle-import") (part "SCHOTTKYSMB"))
    )
    (comp (ref "IC9")
      (value "TL072D")
      (footprint "eagle-import:SOIC127P600X173-8N")
      (libsource (lib "eagle-import") (part "TL072SOIC8"))
    )
    (comp (ref "IC10")
      (value "TL072D")
      (footprint "eagle-import:SOIC127P600X173-8N")
      (libsource (lib "eagle-import") (part "TL072SOIC8"))
    )
    (comp (ref "IC11")
      (value "LTC2050HVCS8#PBF")
      (footprint "eagle-import:SOIC127P600X173-8N")
      (libsource (lib "eagle-import") (part "OP27GSZSO8"))
    )
    (comp (ref "IC12")
      (value "SN74LVC1G3157DCKR")
      (footprint "eagle-import:SOT65P210X110-6N")
      (libsource (lib "eagle-import") (part "SN74LVC1G3157-DCK"))
    )
    (comp (ref "KK3")
      (value "SK96/84")
      (footprint "eagle-import:SK96_84")
      (libsource (lib "eagle-import") (part "SK96/84"))
    )
    (comp (ref "Q4")
      (value "D45H11FP")
      (footprint "eagle-import:TO220FP-V")
      (libsource (lib "eagle-import") (part "D45H11-FPV"))
    )
    (comp (ref "Q5")
      (value "D45H11FP")
      (footprint "eagle-import:TO220FP-V")
      (libsource (lib "eagle-import") (part "D45H11-FPV"))
    )
    (comp (ref "Q6")
      (value "FQPF11P06 or FQPF27P06")
      (footprint "eagle-import:TO220FP-V")
      (libsource (lib "eagle-import") (part "P-MOSFET-FPV"))
    )
    (comp (ref "Q7")
      (value "BCP56-16.115")
      (footprint "eagle-import:SOT230P700X180-4N")
      (libsource (lib "eagle-import") (part "BCP56"))
    )
    (comp (ref "Q8")
      (value "MMBT5401")
      (footprint "eagle-import:SOT23-BEC")
      (libsource (lib "eagle-import") (part "-PNP-SOT23-BECBC857B"))
    )
    (comp (ref "Q9")
      (value "NZT605")
      (footprint "eagle-import:SOT230P700X180-4N")
      (libsource (lib "eagle-import") (part "NZT605"))
    )
    (comp (ref "Q10")
      (value "2N7002")
      (footprint "eagle-import:SOT103P240X110-3N")
      (fields (field (name "MPN") "2N7002-7-F"))
      (libsource (lib "eagle-import") (part "2N7002"))
    )
    (comp (ref "Q11")
      (value "BSS205NH6327XTSA1")
      (footprint "eagle-import:SOT103P240X110-3N")
      (fields
        (field (name "MPN") "2N7002-7-F")
        (field (name "MPN_1") "2N7002-7-F")
        (field (name "OC_FARNELL") "1713823")
        (field (name "OC_NEWARK") "25R5679")
        (field (name "PACKAGE") "SOT-23-3")
        (field (name "SUPPLIER") "DIODES INC.")
      )
      (libsource (lib "eagle-import") (part "2N7002"))
    )
    (comp (ref "Q12")
      (value "PSMN0R9-25YLC")
      (footprint "eagle-import:SOT669")
      (libsource (lib "eagle-import") (part "N-MOSFETLFPAK"))
    )
    (comp (ref "Q13")
      (value "PSMN0R9-25YLC")
      (footprint "eagle-import:SOT669")
      (libsource (lib "eagle-import") (part "N-MOSFETLFPAK"))
    )
    (comp (ref "R25")
      (value "0R1/2-3W")
      (footprint "eagle-import:R2512")
      (libsource (lib "eagle-import") (part "R-EU_R2512"))
    )
    (comp (ref "R26")
      (value "2R2/2W")
      (footprint "eagle-import:R2512")
      (libsource (lib "eagle-import") (part "R-EU_R2512"))
    )
    (comp (ref "R27")
      (value "4K7")
      (footprint "eagle-import:R0805")
      (libsource (lib "eagle-import") (part "R-EU_R0805"))
    )
    (comp (ref "R28")
      (value "4K7")
      (footprint "eagle-import:R0805")
      (libsource (lib "eagle-import") (part "R-EU_R0805"))
    )
    (comp (ref "R29")
      (value "0R1/2-3W")
      (footprint "eagle-import:R2512")
      (libsource (lib "eagle-import") (part "R-EU_R2512"))
    )
    (comp (ref "R30")
      (value "4K7")
      (footprint "eagle-import:R0805")
      (libsource (lib "eagle-import") (part "R-EU_R0805"))
    )
    (comp (ref "R31")
      (value "10K")
      (footprint "eagle-import:R0805")
      (libsource (lib "eagle-import") (part "R-EU_R0805"))
    )
    (comp (ref "R32")
      (value "2K2")
      (footprint "eagle-import:R0805")
      (libsource (lib "eagle-import") (part "R-EU_R0805"))
    )
    (comp (ref "R33")
      (value "10R")
      (footprint "eagle-import:R1206")
      (libsource (lib "eagle-import") (part "R-EU_R1206"))
    )
    (comp (ref "R34")
      (value "10R")
      (footprint "eagle-import:R1206")
      (libsource (lib "eagle-import") (part "R-EU_R1206"))
    )
    (comp (ref "R35")
      (value "4K7")
      (footprint "eagle-import:R0805")
      (libsource (lib "eagle-import") (part "R-EU_R0805"))
    )
    (comp (ref "R36")
      (value "1K")
      (footprint "eagle-import:R0805")
      (libsource (lib "eagle-import") (part "R-EU_R0805"))
    )
    (comp (ref "R37")
      (value "220R")
      (footprint "eagle-import:R0805")
      (libsource (lib "eagle-import") (part "R-EU_R0805"))
    )
    (comp (ref "R38")
      (value "220R")
      (footprint "eagle-import:R0805")
      (libsource (lib "eagle-import") (part "R-EU_R0805"))
    )
    (comp (ref "R39")
      (value "22K")
      (footprint "eagle-import:R0805")
      (libsource (lib "eagle-import") (part "R-EU_R0805"))
    )
    (comp (ref "R40")
      (value "2K2")
      (footprint "eagle-import:R0805")
      (libsource (lib "eagle-import") (part "R-EU_R0805"))
    )
    (comp (ref "R41")
      (value "10K")
      (footprint "eagle-import:R0805")
      (libsource (lib "eagle-import") (part "R-EU_R0805"))
    )
    (comp (ref "R42")
      (value "7K5 0.1%")
      (footprint "eagle-import:R0805")
      (libsource (lib "eagle-import") (part "R-EU_R0805"))
    )
    (comp (ref "R43")
      (value "1K")
      (footprint "eagle-import:R0805")
      (libsource (lib "eagle-import") (part "R-EU_R0805"))
    )
    (comp (ref "R44")
      (value "10K")
      (footprint "eagle-import:R0805")
      (libsource (lib "eagle-import") (part "R-EU_R0805"))
    )
    (comp (ref "R45")
      (value "2K2")
      (footprint "eagle-import:R0805")
      (libsource (lib "eagle-import") (part "R-EU_R0805"))
    )
    (comp (ref "R46")
      (value "22K")
      (footprint "eagle-import:R0805")
      (libsource (lib "eagle-import") (part "R-EU_R0805"))
    )
    (comp (ref "R47")
      (value "124K 0.1%")
      (footprint "eagle-import:R0805")
      (libsource (lib "eagle-import") (part "R-EU_R0805"))
    )
    (comp (ref "R48")
      (value "124K 0.1%")
      (footprint "eagle-import:R0805")
      (libsource (lib "eagle-import") (part "R-EU_R0805"))
    )
    (comp (ref "R49")
      (value "7K5 0.1%")
      (footprint "eagle-import:R0805")
      (libsource (lib "eagle-import") (part "R-EU_R0805"))
    )
    (comp (ref "R50")
      (value "15R")
      (footprint "eagle-import:R2010")
      (libsource (lib "eagle-import") (part "R-EU_R2010"))
    )
    (comp (ref "R51")
      (value "N.C.")
      (footprint "eagle-import:R0805")
      (libsource (lib "eagle-import") (part "R-EU_R0805"))
    )
    (comp (ref "R52")
      (value "10K")
      (footprint "eagle-import:R0805")
      (libsource (lib "eagle-import") (part "R-EU_R0805"))
    )
    (comp (ref "R53")
      (value "10K")
      (footprint "eagle-import:R0805")
      (libsource (lib "eagle-import") (part "R-EU_R0805"))
    )
    (comp (ref "R54")
      (value "220R")
      (footprint "eagle-import:R0805")
      (libsource (lib "eagle-import") (part "R-EU_R0805"))
    )
    (comp (ref "R55")
      (value "100K")
      (footprint "eagle-import:R0805")
      (libsource (lib "eagle-import") (part "R-EU_R0805"))
    )
    (comp (ref "R56")
      (value "2K2")
      (footprint "eagle-import:R0805")
      (libsource (lib "eagle-import") (part "R-EU_R0805"))
    )
    (comp (ref "R57")
      (value "2K2")
      (footprint "eagle-import:R0805")
      (libsource (lib "eagle-import") (part "R-EU_R0805"))
    )
    (comp (ref "R58")
      (value "39K 0.1%")
      (footprint "eagle-import:R0805")
      (libsource (lib "eagle-import") (part "R-EU_R0805"))
    )
    (comp (ref "R59")
      (value "820R 0.1%")
      (footprint "eagle-import:R0805")
      (libsource (lib "eagle-import") (part "R-EU_R0805"))
    )
    (comp (ref "R60")
      (value "47K")
      (footprint "eagle-import:R0805")
      (libsource (lib "eagle-import") (part "R-EU_R0805"))
    )
    (comp (ref "R61")
      (value "1R")
      (footprint "eagle-import:R1206")
      (libsource (lib "eagle-import") (part "R-EU_R1206"))
    )
    (comp (ref "R62")
      (value "22K")
      (footprint "eagle-import:R0805")
      (libsource (lib "eagle-import") (part "R-EU_R0805"))
    )
    (comp (ref "R63")
      (value "8K2")
      (footprint "eagle-import:R0805")
      (libsource (lib "eagle-import") (part "R-EU_R0805"))
    )
    (comp (ref "R64")
      (value "470R")
      (footprint "eagle-import:R0805")
      (libsource (lib "eagle-import") (part "R-EU_R0805"))
    )
    (comp (ref "R65")
      (value "39K 0.1%")
      (footprint "eagle-import:R0805")
      (libsource (lib "eagle-import") (part "R-EU_R0805"))
    )
    (comp (ref "R66")
      (value "47K")
      (footprint "eagle-import:R0805")
      (libsource (lib "eagle-import") (part "R-EU_R0805"))
    )
    (comp (ref "R67")
      (value "0R010 (low TCR)")
      (footprint "eagle-import:R_2512-4WIRE")
      (libsource (lib "eagle-import") (part "R-EU_4WIRE2512"))
    )
    (comp (ref "R68")
      (value "820R 0.1%")
      (footprint "eagle-import:R0805")
      (libsource (lib "eagle-import") (part "R-EU_R0805"))
    )
    (comp (ref "R69")
      (value "1K")
      (footprint "eagle-import:R0805")
      (libsource (lib "eagle-import") (part "R-EU_R0805"))
    )
    (comp (ref "ZD2")
      (value "MM3Z9V1T1G")
      (footprint "eagle-import:SOD323-R")
      (libsource (lib "eagle-import") (part "ZENER-DIODESOD323R"))
    )
    (comp (ref "C88")
      (value "10n")
      (footprint "eagle-import:C0805")
      (libsource (lib "eagle-import") (part "C-EUC0805"))
    )
    (comp (ref "C89")
      (value "470n")
      (footprint "eagle-import:C0805")
      (libsource (lib "eagle-import") (part "C-EUC0805"))
    )
    (comp (ref "C90")
      (value "HHXC630A330MHA0")
      (footprint "eagle-import:CAPAE830X1050N")
      (libsource (lib "eagle-import") (part "ECAPSMD8.3MM/HA0"))
    )
    (comp (ref "C91")
      (value "10n/200V")
      (footprint "eagle-import:C1206")
      (libsource (lib "eagle-import") (part "C-EUC1206"))
    )
    (comp (ref "C92")
      (value "10n/200V")
      (footprint "eagle-import:C1206")
      (libsource (lib "eagle-import") (part "C-EUC1206"))
    )
    (comp (ref "C93")
      (value "10n")
      (footprint "eagle-import:C0805")
      (libsource (lib "eagle-import") (part "C-EUC0805"))
    )
    (comp (ref "D19")
      (value "BAS316")
      (footprint "eagle-import:SOD323-R")
      (libsource (lib "eagle-import") (part "DIODESOD323R"))
    )
    (comp (ref "F1")
      (value "ZH32")
      (footprint "eagle-import:ZH32")
      (libsource (lib "eagle-import") (part "ZH32"))
    )
    (comp (ref "F2")
      (value "ZH32")
      (footprint "eagle-import:ZH32")
      (libsource (lib "eagle-import") (part "ZH32"))
    )
    (comp (ref "J2")
      (value "FCR7350R")
      (footprint "eagle-import:S16N-PC")
      (libsource (lib "eagle-import") (part "BINDING_POSTCLIFF"))
    )
    (comp (ref "J3")
      (value "FCR7350B")
      (footprint "eagle-import:S16N-PC")
      (libsource (lib "eagle-import") (part "BINDING_POSTCLIFF"))
    )
    (comp (ref "K1")
      (value "FTR-C1GA005G-B05")
      (footprint "eagle-import:FTR-C1")
      (libsource (lib "eagle-import") (part "FTR-C1"))
    )
    (comp (ref "LED2")
      (value "WP934MD/2LID")
      (footprint "eagle-import:WP934MD")
      (libsource (lib "eagle-import") (part "WP934MD/2LID"))
    )
    (comp (ref "Q22")
      (value "MMBT5401")
      (footprint "eagle-import:SOT23-BEC")
      (libsource (lib "eagle-import") (part "-PNP-SOT23-BECBC857B"))
    )
    (comp (ref "Q23")
      (value "MMBT5551")
      (footprint "eagle-import:SOT23-BEC")
      (libsource (lib "eagle-import") (part "-NPN-SOT23-BECMMBT5551LT1"))
    )
    (comp (ref "Q24")
      (value "MMBT5551")
      (footprint "eagle-import:SOT23-BEC")
      (libsource (lib "eagle-import") (part "-NPN-SOT23-BECMMBT5551LT1"))
    )
    (comp (ref "Q25")
      (value "2N7002")
      (footprint "eagle-import:SOT103P240X110-3N")
      (fields (field (name "MPN") "2N7002-7-F"))
      (libsource (lib "eagle-import") (part "2N7002"))
    )
    (comp (ref "R105")
      (value "330R")
      (footprint "eagle-import:R0805")
      (libsource (lib "eagle-import") (part "R-EU_R0805"))
    )
    (comp (ref "R106")
      (value "750R")
      (footprint "eagle-import:R0805")
      (libsource (lib "eagle-import") (part "R-EU_R0805"))
    )
    (comp (ref "R107")
      (value "3K3")
      (footprint "eagle-import:R0805")
      (libsource (lib "eagle-import") (part "R-EU_R0805"))
    )
    (comp (ref "R108")
      (value "10K")
      (footprint "eagle-import:R0805")
      (libsource (lib "eagle-import") (part "R-EU_R0805"))
    )
    (comp (ref "R109")
      (value "10K")
      (footprint "eagle-import:R0805")
      (libsource (lib "eagle-import") (part "R-EU_R0805"))
    )
    (comp (ref "R110")
      (value "1R")
      (footprint "eagle-import:R1206")
      (libsource (lib "eagle-import") (part "R-EU_R1206"))
    )
    (comp (ref "R111")
      (value "750R")
      (footprint "eagle-import:R0805")
      (libsource (lib "eagle-import") (part "R-EU_R0805"))
    )
    (comp (ref "R112")
      (value "47K")
      (footprint "eagle-import:R0805")
      (libsource (lib "eagle-import") (part "R-EU_R0805"))
    )
    (comp (ref "R113")
      (value "330R")
      (footprint "eagle-import:R0805")
      (libsource (lib "eagle-import") (part "R-EU_R0805"))
    )
    (comp (ref "R114")
      (value "470R")
      (footprint "eagle-import:R0805")
      (libsource (lib "eagle-import") (part "R-EU_R0805"))
    )
    (comp (ref "R115")
      (value "100K")
      (footprint "eagle-import:R0805")
      (libsource (lib "eagle-import") (part "R-EU_R0805"))
    )
    (comp (ref "X3")
      (value "691322110005")
      (footprint "eagle-import:MC1,5_5-G-3,5")
      (libsource (lib "eagle-import") (part "MC1,5/5-G-3,5"))
    )
    (comp (ref "X4")
      (value "DS1024-2*10R0")
      (footprint "eagle-import:SSW-110-02-T-D-RA")
      (libsource (lib "eagle-import") (part "SSW-110-02-T-D-RA"))
    )
    (comp (ref "ZD5")
      (value "SMAJ51A")
      (footprint "eagle-import:DO214AA")
      (libsource (lib "eagle-import") (part "P6SMB68A"))
    )
    (comp (ref "C64")
      (value "100n")
      (footprint "eagle-import:C0603")
      (libsource (lib "eagle-import") (part "C-EUC0603"))
    )
    (comp (ref "C65")
      (value "100n")
      (footprint "eagle-import:C0603")
      (libsource (lib "eagle-import") (part "C-EUC0603"))
    )
    (comp (ref "C66")
      (value "4u7")
      (footprint "eagle-import:C1206")
      (libsource (lib "eagle-import") (part "C-EUC1206"))
    )
    (comp (ref "C67")
      (value "100n")
      (footprint "eagle-import:C0603")
      (libsource (lib "eagle-import") (part "C-EUC0603"))
    )
    (comp (ref "C68")
      (value "4u7 tant.")
      (footprint "eagle-import:EC1206")
      (libsource (lib "eagle-import") (part "ECAP1206"))
    )
    (comp (ref "C69")
      (value "1u")
      (footprint "eagle-import:C0805")
      (libsource (lib "eagle-import") (part "C-EUC0805"))
    )
    (comp (ref "C70")
      (value "1u")
      (footprint "eagle-import:C0805")
      (libsource (lib "eagle-import") (part "C-EUC0805"))
    )
    (comp (ref "C71")
      (value "100n")
      (footprint "eagle-import:C0603")
      (libsource (lib "eagle-import") (part "C-EUC0603"))
    )
    (comp (ref "C72")
      (value "100n")
      (footprint "eagle-import:C0603")
      (libsource (lib "eagle-import") (part "C-EUC0603"))
    )
    (comp (ref "C73")
      (value "100n")
      (footprint "eagle-import:C0603")
      (libsource (lib "eagle-import") (part "C-EUC0603"))
    )
    (comp (ref "C74")
      (value "4n7")
      (footprint "eagle-import:C0805")
      (libsource (lib "eagle-import") (part "C-EUC0805"))
    )
    (comp (ref "C75")
      (value "4n7")
      (footprint "eagle-import:C0805")
      (libsource (lib "eagle-import") (part "C-EUC0805"))
    )
    (comp (ref "C76")
      (value "4n7")
      (footprint "eagle-import:C0805")
      (libsource (lib "eagle-import") (part "C-EUC0805"))
    )
    (comp (ref "C77")
      (value "4n7")
      (footprint "eagle-import:C0805")
      (libsource (lib "eagle-import") (part "C-EUC0805"))
    )
    (comp (ref "C78")
      (value "100n")
      (footprint "eagle-import:C0603")
      (libsource (lib "eagle-import") (part "C-EUC0603"))
    )
    (comp (ref "C79")
      (value "1u")
      (footprint "eagle-import:C0805")
      (libsource (lib "eagle-import") (part "C-EUC0805"))
    )
    (comp (ref "C80")
      (value "100n")
      (footprint "eagle-import:C0603")
      (libsource (lib "eagle-import") (part "C-EUC0603"))
    )
    (comp (ref "C81")
      (value "1u")
      (footprint "eagle-import:C0805")
      (libsource (lib "eagle-import") (part "C-EUC0805"))
    )
    (comp (ref "C82")
      (value "100n")
      (footprint "eagle-import:C0603")
      (libsource (lib "eagle-import") (part "C-EUC0603"))
    )
    (comp (ref "D15")
      (value "BAS316")
      (footprint "eagle-import:SOD323-R")
      (libsource (lib "eagle-import") (part "DIODESOD323R"))
    )
    (comp (ref "D16")
      (value "N.C.")
      (footprint "eagle-import:SOD323-R")
      (libsource (lib "eagle-import") (part "DIODESOD323R"))
    )
    (comp (ref "IC13")
      (value "74AUP1G74DC.125")
      (footprint "eagle-import:DCU8")
      (libsource (lib "eagle-import") (part "SN74LVC1G74DCTR-VSSOP"))
    )
    (comp (ref "IC14")
      (value "MCP23S17-E/SS")
      (footprint "eagle-import:SOP65P780X200-28N")
      (libsource (lib "eagle-import") (part "MCP23S17-E/SSSSOP"))
    )
    (comp (ref "IC15")
      (value "REF5025AIDR")
      (footprint "eagle-import:SOIC127P600X175-8N")
      (libsource (lib "eagle-import") (part "REF50XX"))
    )
    (comp (ref "IC16")
      (value "TC77-5.0MCTTR")
      (footprint "eagle-import:SOT23-5")
      (libsource (lib "eagle-import") (part "TC77"))
    )
    (comp (ref "IC17")
      (value "DAC8552IDGKR")
      (footprint "eagle-import:DGK8-M")
      (libsource (lib "eagle-import") (part "DAC8552_DGK_8M"))
    )
    (comp (ref "IC18")
      (value "SN74LVC1G3157DCKR")
      (footprint "eagle-import:SOT65P210X110-6N")
      (libsource (lib "eagle-import") (part "SN74LVC1G3157-DCK"))
    )
    (comp (ref "IC19")
      (value "ADS1120IPWR")
      (footprint "eagle-import:PW(R-PDSO-G16)")
      (libsource (lib "eagle-import") (part "ADS1120TSSOP-16"))
    )
    (comp (ref "LED1")
      (value "WP42WUM/EGW")
      (footprint "eagle-import:L-42WUM-1EGWT")
      (libsource (lib "eagle-import") (part "LED_L-42WUM/1EGWT"))
    )
    (comp (ref "OE")
      (value "JP2-NOCUT")
      (footprint "eagle-import:JP2-NOCUT")
      (libsource (lib "eagle-import") (part "JP2-NOCUT"))
    )
    (comp (ref "Q14")
      (value "BSS84P")
      (footprint "eagle-import:SOT95P237X112-3N")
      (fields (field (name "MPN") "IRLML2246TRPBF"))
      (libsource (lib "eagle-import") (part "IRLML2246TRPBF"))
    )
    (comp (ref "R70")
      (value "1K")
      (footprint "eagle-import:R0805")
      (libsource (lib "eagle-import") (part "R-EU_R0805"))
    )
    (comp (ref "R71")
      (value "10K")
      (footprint "eagle-import:R0805")
      (libsource (lib "eagle-import") (part "R-EU_R0805"))
    )
    (comp (ref "R72")
      (value "100K")
      (footprint "eagle-import:R0805")
      (libsource (lib "eagle-import") (part "R-EU_R0805"))
    )
    (comp (ref "R73")
      (value "270R")
      (footprint "eagle-import:R0805")
      (libsource (lib "eagle-import") (part "R-EU_R0805"))
    )
    (comp (ref "R74")
      (value "2K2")
      (footprint "eagle-import:R0805")
      (libsource (lib "eagle-import") (part "R-EU_R0805"))
    )
    (comp (ref "R75")
      (value "470R")
      (footprint "eagle-import:R0805")
      (libsource (lib "eagle-import") (part "R-EU_R0805"))
    )
    (comp (ref "R76")
      (value "470R")
      (footprint "eagle-import:R0805")
      (libsource (lib "eagle-import") (part "R-EU_R0805"))
    )
    (comp (ref "R77")
      (value "2K2")
      (footprint "eagle-import:R0805")
      (libsource (lib "eagle-import") (part "R-EU_R0805"))
    )
    (comp (ref "R78")
      (value "2K2")
      (footprint "eagle-import:R0805")
      (libsource (lib "eagle-import") (part "R-EU_R0805"))
    )
    (comp (ref "R79")
      (value "470R")
      (footprint "eagle-import:R0805")
      (libsource (lib "eagle-import") (part "R-EU_R0805"))
    )
    (comp (ref "R80")
      (value "2K2")
      (footprint "eagle-import:R0805")
      (libsource (lib "eagle-import") (part "R-EU_R0805"))
    )
    (comp (ref "R81")
      (value "2K2")
      (footprint "eagle-import:R0805")
      (libsource (lib "eagle-import") (part "R-EU_R0805"))
    )
    (comp (ref "R82")
      (value "10R")
      (footprint "eagle-import:R1206")
      (libsource (lib "eagle-import") (part "R-EU_R1206"))
    )
    (comp (ref "ZD3")
      (value "SLVU2.8-TP")
      (footprint "eagle-import:SOT23")
      (libsource (lib "eagle-import") (part "SLVU2.8"))
    )
  )
  (nets
    (net (code "1") (name "+3V3") (class "Default")
      (node (ref "C33") (pin "1") (pinfunction "1_1") (pintype "passive"))
      (node (ref "C38") (pin "1") (pinfunction "1_1") (pintype "passive"))
      (node (ref "C41") (pin "2") (pinfunction "2_2") (pintype "passive"))
      (node (ref "IC3") (pin "1") (pinfunction "VDD1_1") (pintype "passive"))
      (node (ref "IC3") (pin "7") (pinfunction "EN1_7") (pintype "input"))
      (node (ref "IC7") (pin "1") (pinfunction "VDD1_1") (pintype "passive"))
      (node (ref "IC7") (pin "7") (pinfunction "EN1_7") (pintype "input"))
      (node (ref "IC8") (pin "8") (pinfunction "VCC_8") (pintype "power_in"))
      (node (ref "R22") (pin "1") (pinfunction "1_1") (pintype "passive"))
      (node (ref "R23") (pin "1") (pinfunction "1_1") (pintype "passive"))
      (node (ref "R24") (pin "1") (pinfunction "1_1") (pintype "passive"))
      (node (ref "X2") (pin "1") (pinfunction "1_1") (pintype "passive"))
    )
    (net (code "2") (name "+5V") (class "Default")
      (node (ref "C34") (pin "2") (pinfunction "2_2") (pintype "passive"))
      (node (ref "C35") (pin "1") (pinfunction "1_1") (pintype "passive"))
      (node (ref "C39") (pin "2") (pinfunction "2_2") (pintype "passive"))
      (node (ref "C64") (pin "2") (pinfunction "2_2") (pintype "passive"))
      (node (ref "C65") (pin "1") (pinfunction "1_1") (pintype "passive"))
      (node (ref "C67") (pin "1") (pinfunction "1_1") (pintype "passive"))
      (node (ref "C78") (pin "2") (pinfunction "2_2") (pintype "passive"))
      (node (ref "C79") (pin "2") (pinfunction "2_2") (pintype "passive"))
      (node (ref "C86") (pin "1") (pinfunction "1_1") (pintype "passive"))
      (node (ref "D19") (pin "C") (pinfunction "C_C") (pintype "passive"))
      (node (ref "FB2") (pin "P$2") (pinfunction "2_P$2") (pintype "passive"))
      (node (ref "IC13") (pin "7") (pinfunction "~{PRE}_7") (pintype "input"))
      (node (ref "IC13") (pin "8") (pinfunction "VDD_8") (pintype "power_in"))
      (node (ref "IC14") (pin "9") (pinfunction "VDD_9") (pintype "power_in"))
      (node (ref "IC16") (pin "5") (pinfunction "VDD_5") (pintype "passive"))
      (node (ref "IC19") (pin "13") (pinfunction "DVDD_13") (pintype "power_in"))
      (node (ref "IC3") (pin "10") (pinfunction "EN2_10") (pintype "input"))
      (node (ref "IC3") (pin "16") (pinfunction "VDD2_16") (pintype "passive"))
      (node (ref "IC4") (pin "8") (pinfunction "VCC_8") (pintype "passive"))
      (node (ref "IC7") (pin "10") (pinfunction "EN2_10") (pintype "input"))
      (node (ref "IC7") (pin "16") (pinfunction "VDD2_16") (pintype "passive"))
      (node (ref "K1") (pin "1") (pinfunction "C1_1") (pintype "passive"))
      (node (ref "LED2") (pin "TA") (pinfunction "A_TA") (pintype "passive"))
      (node (ref "LED3") (pin "BA") (pinfunction "A_BA") (pintype "passive"))
      (node (ref "LED3") (pin "TA") (pinfunction "A_TA") (pintype "passive"))
      (node (ref "Q14") (pin "2") (pinfunction "S_2") (pintype "passive"))
      (node (ref "R102") (pin "1") (pinfunction "1_1") (pintype "passive"))
      (node (ref "R108") (pin "2") (pinfunction "2_2") (pintype "passive"))
      (node (ref "R17") (pin "1") (pinfunction "1_1") (pintype "passive"))
      (node (ref "R70") (pin "1") (pinfunction "1_1") (pintype "passive"))
      (node (ref "R71") (pin "1") (pinfunction "1_1") (pintype "passive"))
      (node (ref "R72") (pin "1") (pinfunction "1_1") (pintype "passive"))
      (node (ref "R84") (pin "2") (pinfunction "2_2") (pintype "passive"))
      (node (ref "R96") (pin "2") (pinfunction "2_2") (pintype "passive"))
    )
    (net (code "3") (name "+VNR") (class "Default")
      (node (ref "C30") (pin "1") (pinfunction "1_1") (pintype "passive"))
      (node (ref "D2") (pin "A") (pinfunction "A_A") (pintype "passive"))
      (node (ref "IC5") (pin "8") (pinfunction "VI_8") (pintype "input"))
      (node (ref "R14") (pin "1") (pinfunction "1_1") (pintype "passive"))
    )
    (net (code "4") (name "+VREF") (class "Default")
      (node (ref "C68") (pin "+") (pinfunction "+_+") (pintype "passive"))
      (node (ref "C72") (pin "2") (pinfunction "2_2") (pintype "passive"))
      (node (ref "C82") (pin "2") (pinfunction "2_2") (pintype "passive"))
      (node (ref "IC15") (pin "6") (pinfunction "VOUT_6") (pintype "output"))
      (node (ref "IC17") (pin "2") (pinfunction "VREF_2") (pintype "input"))
      (node (ref "IC19") (pin "9") (pinfunction "REFP0_9") (pintype "input"))
      (node (ref "R31") (pin "1") (pinfunction "1_1") (pintype "passive"))
    )
    (net (code "5") (name "-9V") (class "Default")
      (node (ref "C24") (pin "1") (pinfunction "1_1") (pintype "passive"))
      (node (ref "IC6") (pin "2") (pinfunction "IN_2") (pintype "input"))
      (node (ref "IC6") (pin "3") (pinfunction "IN_3") (pintype "input"))
      (node (ref "IC6") (pin "6") (pinfunction "IN_6") (pintype "input"))
      (node (ref "IC6") (pin "7") (pinfunction "IN_7") (pintype "input"))
      (node (ref "R12") (pin "1") (pinfunction "1_1") (pintype "passive"))
      (node (ref "R36") (pin "2") (pinfunction "2_2") (pintype "passive"))
      (node (ref "R37") (pin "2") (pinfunction "2_2") (pintype "passive"))
    )
    (net (code "6") (name "AGND") (class "Default")
      (node (ref "C21") (pin "2") (pinfunction "2_2") (pintype "passive"))
      (node (ref "IC1") (pin "6") (pinfunction "AGND_6") (pintype "power_in"))
      (node (ref "R11") (pin "2") (pinfunction "2_2") (pintype "passive"))
      (node (ref "R3") (pin "1") (pinfunction "1_1") (pintype "passive"))
      (node (ref "R9") (pin "1") (pinfunction "1_1") (pintype "passive"))
      (node (ref "SH2") (pin "1") (pinfunction "GND_A_1") (pintype "bidirectional"))
    )
    (net (code "7") (name "AUX_USET_SW") (class "Default")
      (node (ref "IC14") (pin "4") (pinfunction "GPB3_4") (pintype "bidirectional"))
      (node (ref "IC18") (pin "6") (pinfunction "CTRL_6") (pintype "input"))
      (node (ref "LED2") (pin "BA") (pinfunction "A_BA") (pintype "passive"))
    )
    (net (code "8") (name "CC_ACTIVE") (class "Default")
      (node (ref "IC14") (pin "22") (pinfunction "GPA1_22") (pintype "bidirectional"))
      (node (ref "Q10") (pin "1") (pinfunction "G_1") (pintype "passive"))
      (node (ref "Q18") (pin "1") (pinfunction "G_1") (pintype "passive"))
      (node (ref "R100") (pin "2") (pinfunction "2_2") (pintype "passive"))
      (node (ref "R96") (pin "1") (pinfunction "1_1") (pintype "passive"))
    )
    (net (code "9") (name "CSA") (class "Default")
      (node (ref "IC3") (pin "13") (pinfunction "B2_13") (pintype "output"))
      (node (ref "IC4") (pin "1") (pinfunction "A_1") (pintype "input"))
    )
    (net (code "10") (name "CSB") (class "Default")
      (node (ref "IC3") (pin "12") (pinfunction "B3_12") (pintype "output"))
      (node (ref "IC4") (pin "2") (pinfunction "B_2") (pintype "input"))
    )
    (net (code "11") (name "CS_ADC") (class "Default")
      (node (ref "IC19") (pin "2") (pinfunction "~{CS}_2") (pintype "input"))
      (node (ref "RN2") (pin "7") (pinfunction "2_7") (pintype "passive"))
    )
    (net (code "12") (name "CS_DAC") (class "Default")
      (node (ref "IC17") (pin "5") (pinfunction "~{SYNC}_5") (pintype "input"))
      (node (ref "RN2") (pin "8") (pinfunction "2_8") (pintype "passive"))
    )
    (net (code "13") (name "CS_IOEXP") (class "Default")
      (node (ref "IC14") (pin "11") (pinfunction "~{CS}_11") (pintype "input"))
      (node (ref "RN2") (pin "6") (pinfunction "2_6") (pintype "passive"))
    )
    (net (code "14") (name "CURR_5A") (class "Default")
      (node (ref "IC12") (pin "6") (pinfunction "CTRL_6") (pintype "input"))
      (node (ref "IC14") (pin "28") (pinfunction "GPA7_28") (pintype "bidirectional"))
      (node (ref "Q13") (pin "4") (pinfunction "G_4") (pintype "passive"))
      (node (ref "R66") (pin "2") (pinfunction "2_2") (pintype "passive"))
    )
    (net (code "15") (name "CURR_50MA") (class "Default")
      (node (ref "IC14") (pin "27") (pinfunction "GPA6_27") (pintype "bidirectional"))
      (node (ref "Q12") (pin "4") (pinfunction "G_4") (pintype "passive"))
      (node (ref "R60") (pin "2") (pinfunction "2_2") (pintype "passive"))
    )
    (net (code "16") (name "CV_ACTIVE") (class "Default")
      (node (ref "IC14") (pin "23") (pinfunction "GPA2_23") (pintype "bidirectional"))
      (node (ref "Q16") (pin "1") (pinfunction "G_1") (pintype "passive"))
      (node (ref "R84") (pin "1") (pinfunction "1_1") (pintype "passive"))
      (node (ref "R86") (pin "2") (pinfunction "2_2") (pintype "passive"))
    )
    (net (code "17") (name "DC+") (class "Default")
      (node (ref "C1") (pin "2") (pinfunction "2_2") (pintype "passive"))
      (node (ref "L1") (pin "1") (pinfunction "1_1") (pintype "passive"))
      (node (ref "R1") (pin "2") (pinfunction "2_2") (pintype "passive"))
      (node (ref "X1") (pin "1") (pinfunction "1_1") (pintype "passive"))
    )
    (net (code "18") (name "DC-") (class "Default")
      (node (ref "C1") (pin "1") (pinfunction "1_1") (pintype "passive"))
      (node (ref "L1") (pin "3") (pinfunction "1_3") (pintype "passive"))
      (node (ref "R1") (pin "1") (pinfunction "1_1") (pintype "passive"))
      (node (ref "X1") (pin "2") (pinfunction "1_2") (pintype "passive"))
    )
    (net (code "19") (name "DC_OUT") (class "Default")
      (node (ref "C25") (pin "1") (pinfunction "1_1") (pintype "passive"))
      (node (ref "C26") (pin "1") (pinfunction "1_1") (pintype "passive"))
      (node (ref "C3") (pin "2") (pinfunction "2_2") (pintype "passive"))
      (node (ref "C4") (pin "+") (pinfunction "+_+") (pintype "passive"))
      (node (ref "C5") (pin "1") (pinfunction "1_1") (pintype "passive"))
      (node (ref "C6") (pin "1") (pinfunction "1_1") (pintype "passive"))
      (node (ref "C7") (pin "1") (pinfunction "1_1") (pintype "passive"))
      (node (ref "C7A") (pin "2") (pinfunction "2_2") (pintype "passive"))
      (node (ref "C9") (pin "2") (pinfunction "2_2") (pintype "passive"))
      (node (ref "IC1") (pin "20") (pinfunction "VIN_20") (pintype "power_in"))
      (node (ref "IC2") (pin "2") (pinfunction "VIN_2") (pintype "power_in"))
      (node (ref "L1") (pin "2") (pinfunction "2_2") (pintype "passive"))
      (node (ref "Q1") (pin "5") (pinfunction "D_5") (pintype "passive"))
      (node (ref "Q1") (pin "6") (pinfunction "D_6") (pintype "passive"))
      (node (ref "Q1") (pin "7") (pinfunction "D_7") (pintype "passive"))
      (node (ref "Q1") (pin "8") (pinfunction "D_8") (pintype "passive"))
      (node (ref "R13") (pin "2") (pinfunction "2_2") (pintype "passive"))
      (node (ref "ZD1") (pin "C") (pinfunction "C_C") (pintype "passive"))
    )
    (net (code "20") (name "DIB_A0") (class "Default")
      (node (ref "IC8") (pin "1") (pinfunction "A0_1") (pintype "input"))
      (node (ref "R24") (pin "2") (pinfunction "2_2") (pintype "passive"))
      (node (ref "X2") (pin "17") (pinfunction "1_17") (pintype "passive"))
    )
    (net (code "21") (name "DIB_A1") (class "Default")
      (node (ref "IC8") (pin "2") (pinfunction "A1_2") (pintype "input"))
      (node (ref "R23") (pin "2") (pinfunction "2_2") (pintype "passive"))
      (node (ref "X2") (pin "19") (pinfunction "1_19") (pintype "passive"))
    )
    (net (code "22") (name "DIB_A2") (class "Default")
      (node (ref "IC8") (pin "3") (pinfunction "A2_3") (pintype "input"))
      (node (ref "R22") (pin "2") (pinfunction "2_2") (pintype "passive"))
      (node (ref "X2") (pin "18") (pinfunction "1_18") (pintype "passive"))
    )
    (net (code "23") (name "DIB_CSA") (class "Default")
      (node (ref "IC3") (pin "4") (pinfunction "A2_4") (pintype "input"))
      (node (ref "RN1") (pin "2") (pinfunction "1_2") (pintype "passive"))
    )
    (net (code "24") (name "DIB_CSB") (class "Default")
      (node (ref "IC3") (pin "5") (pinfunction "A3_5") (pintype "input"))
      (node (ref "RN1") (pin "1") (pinfunction "1_1") (pintype "passive"))
    )
    (net (code "25") (name "DIB_IRQ") (class "Default")
      (node (ref "IC7") (pin "6") (pinfunction "A4_6") (pintype "output"))
      (node (ref "X2") (pin "10") (pinfunction "1_10") (pintype "passive"))
    )
    (net (code "26") (name "DIB_MISO") (class "Default")
      (node (ref "IC3") (pin "6") (pinfunction "A4_6") (pintype "output"))
      (node (ref "X2") (pin "14") (pinfunction "1_14") (pintype "passive"))
    )
    (net (code "27") (name "DIB_MOSI") (class "Default")
      (node (ref "IC7") (pin "3") (pinfunction "A1_3") (pintype "input"))
      (node (ref "RN1") (pin "3") (pinfunction "1_3") (pintype "passive"))
    )
    (net (code "28") (name "DIB_NRESET") (class "Default")
      (node (ref "X2") (pin "4") (pinfunction "1_4") (pintype "passive"))
    )
    (net (code "29") (name "DIB_SCL") (class "Default")
      (node (ref "IC8") (pin "6") (pinfunction "SCL_6") (pintype "bidirectional"))
      (node (ref "X2") (pin "5") (pinfunction "1_5") (pintype "passive"))
    )
    (net (code "30") (name "DIB_SCLK") (class "Default")
      (node (ref "IC3") (pin "3") (pinfunction "A1_3") (pintype "input"))
      (node (ref "RN1") (pin "4") (pinfunction "1_4") (pintype "passive"))
    )
    (net (code "31") (name "DIB_SDA") (class "Default")
      (node (ref "IC8") (pin "5") (pinfunction "SDA_5") (pintype "bidirectional"))
      (node (ref "X2") (pin "8") (pinfunction "1_8") (pintype "passive"))
    )
    (net (code "32") (name "FB") (class "Default")
      (node (ref "C20") (pin "1") (pinfunction "1_1") (pintype "passive"))
      (node (ref "C22") (pin "1") (pinfunction "1_1") (pintype "passive"))
      (node (ref "IC1") (pin "5") (pinfunction "FB_5") (pintype "input"))
      (node (ref "Q3") (pin "C") (pinfunction "C_C") (pintype "passive"))
      (node (ref "R11") (pin "1") (pinfunction "1_1") (pintype "passive"))
      (node (ref "R6") (pin "2") (pinfunction "2_2") (pintype "passive"))
    )
    (net (code "33") (name "GCOM") (class "Default")
      (node (ref "IC10") (pin "6") (pinfunction "-IN_6") (pintype "input"))
      (node (ref "IC10") (pin "7") (pinfunction "OUT_7") (pintype "output"))
      (node (ref "R42") (pin "1") (pinfunction "1_1") (pintype "passive"))
      (node (ref "R58") (pin "1") (pinfunction "1_1") (pintype "passive"))
    )
    (net (code "34") (name "GND") (class "Default")
      (node (ref "C23") (pin "2") (pinfunction "2_2") (pintype "passive"))
      (node (ref "C24") (pin "2") (pinfunction "2_2") (pintype "passive"))
      (node (ref "C25") (pin "2") (pinfunction "2_2") (pintype "passive"))
      (node (ref "C26") (pin "2") (pinfunction "2_2") (pintype "passive"))
      (node (ref "C29") (pin "2") (pinfunction "2_2") (pintype "passive"))
      (node (ref "C30") (pin "2") (pinfunction "2_2") (pintype "passive"))
      (node (ref "C31") (pin "2") (pinfunction "2_2") (pintype "passive"))
      (node (ref "C32") (pin "1") (pinfunction "1_1") (pintype "passive"))
      (node (ref "C34") (pin "1") (pinfunction "1_1") (pintype "passive"))
      (node (ref "C35") (pin "2") (pinfunction "2_2") (pintype "passive"))
      (node (ref "C36") (pin "1") (pinfunction "1_1") (pintype "passive"))
      (node (ref "C37") (pin "2") (pinfunction "2_2") (pintype "passive"))
      (node (ref "C39") (pin "1") (pinfunction "1_1") (pintype "passive"))
      (node (ref "C40") (pin "1") (pinfunction "1_1") (pintype "passive"))
      (node (ref "C42") (pin "2") (pinfunction "2_2") (pintype "passive"))
      (node (ref "C44") (pin "2") (pinfunction "2_2") (pintype "passive"))
      (node (ref "C48") (pin "2") (pinfunction "2_2") (pintype "passive"))
      (node (ref "C49") (pin "1") (pinfunction "1_1") (pintype "passive"))
      (node (ref "C50") (pin "2") (pinfunction "2_2") (pintype "passive"))
      (node (ref "C51") (pin "1") (pinfunction "1_1") (pintype "passive"))
      (node (ref "C52") (pin "1") (pinfunction "1_1") (pintype "passive"))
      (node (ref "C53") (pin "1") (pinfunction "1_1") (pintype "passive"))
      (node (ref "C54") (pin "1") (pinfunction "1_1") (pintype "passive"))
      (node (ref "C56") (pin "1") (pinfunction "1_1") (pintype "passive"))
      (node (ref "C57") (pin "2") (pinfunction "2_2") (pintype "passive"))
      (node (ref "C58") (pin "1") (pinfunction "1_1") (pintype "passive"))
      (node (ref "C59") (pin "1") (pinfunction "1_1") (pintype "passive"))
      (node (ref "C60") (pin "2") (pinfunction "2_2") (pintype "passive"))
      (node (ref "C64") (pin "1") (pinfunction "1_1") (pintype "passive"))
      (node (ref "C65") (pin "2") (pinfunction "2_2") (pintype "passive"))
      (node (ref "C66") (pin "2") (pinfunction "2_2") (pintype "passive"))
      (node (ref "C67") (pin "2") (pinfunction "2_2") (pintype "passive"))
      (node (ref "C68") (pin "-") (pinfunction "-_-") (pintype "passive"))
      (node (ref "C69") (pin "2") (pinfunction "2_2") (pintype "passive"))
      (node (ref "C70") (pin "2") (pinfunction "2_2") (pintype "passive"))
      (node (ref "C71") (pin "1") (pinfunction "1_1") (pintype "passive"))
      (node (ref "C72") (pin "1") (pinfunction "1_1") (pintype "passive"))
      (node (ref "C73") (pin "2") (pinfunction "2_2") (pintype "passive"))
      (node (ref "C74") (pin "1") (pinfunction "1_1") (pintype "passive"))
      (node (ref "C75") (pin "1") (pinfunction "1_1") (pintype "passive"))
      (node (ref "C76") (pin "2") (pinfunction "2_2") (pintype "passive"))
      (node (ref "C77") (pin "1") (pinfunction "1_1") (pintype "passive"))
      (node (ref "C78") (pin "1") (pinfunction "1_1") (pintype "passive"))
      (node (ref "C79") (pin "1") (pinfunction "1_1") (pintype "passive"))
      (node (ref "C80") (pin "1") (pinfunction "1_1") (pintype "passive"))
      (node (ref "C81") (pin "1") (pinfunction "1_1") (pintype "passive"))
      (node (ref "C82") (pin "1") (pinfunction "1_1") (pintype "passive"))
      (node (ref "C83") (pin "1") (pinfunction "1_1") (pintype "passive"))
      (node (ref "C85") (pin "1") (pinfunction "1_1") (pintype "passive"))
      (node (ref "C87") (pin "1") (pinfunction "1_1") (pintype "passive"))
      (node (ref "D10") (pin "C") (pinfunction "C_C") (pintype "passive"))
      (node (ref "D18") (pin "C") (pinfunction "C_C") (pintype "passive"))
      (node (ref "D5") (pin "A") (pinfunction "A_A") (pintype "passive"))
      (node (ref "D6") (pin "A") (pinfunction "A_A") (pintype "passive"))
      (node (ref "D7") (pin "C") (pinfunction "C_C") (pintype "passive"))
      (node (ref "D9") (pin "C") (pinfunction "C_C") (pintype "passive"))
      (node (ref "GND") (pin "1") (pinfunction "P$1_1") (pintype "bidirectional"))
      (node (ref "IC12") (pin "2") (pinfunction "GND_2") (pintype "passive"))
      (node (ref "IC13") (pin "4") (pinfunction "VSS_4") (pintype "power_in"))
      (node (ref "IC14") (pin "10") (pinfunction "VSS_10") (pintype "power_in"))
      (node (ref "IC14") (pin "15") (pinfunction "A0_15") (pintype "input"))
      (node (ref "IC14") (pin "16") (pinfunction "A1_16") (pintype "input"))
      (node (ref "IC14") (pin "17") (pinfunction "A2_17") (pintype "input"))
      (node (ref "IC15") (pin "4") (pinfunction "GND_4") (pintype "passive"))
      (node (ref "IC16") (pin "2") (pinfunction "GND_2") (pintype "passive"))
      (node (ref "IC17") (pin "8") (pinfunction "GND_8") (pintype "power_in"))
      (node (ref "IC18") (pin "2") (pinfunction "GND_2") (pintype "passive"))
      (node (ref "IC19") (pin "3") (pinfunction "CLK_3") (pintype "bidirectional"))
      (node (ref "IC19") (pin "4") (pinfunction "DGND_4") (pintype "passive"))
      (node (ref "IC19") (pin "5") (pinfunction "AVSS_5") (pintype "passive"))
      (node (ref "IC19") (pin "8") (pinfunction "REFN0_8") (pintype "input"))
      (node (ref "IC2") (pin "9") (pinfunction "GND_9") (pintype "passive"))
      (node (ref "IC2") (pin "TP") (pinfunction "TP_TP") (pintype "passive"))
      (node (ref "IC21") (pin "4") (pinfunction "GND_4") (pintype "passive"))
      (node (ref "IC3") (pin "15") (pinfunction "GND2_15") (pintype "passive"))
      (node (ref "IC3") (pin "9") (pinfunction "GND2_2_9") (pintype "passive"))
      (node (ref "IC4") (pin "4") (pinfunction "GND_4") (pintype "passive"))
      (node (ref "IC5") (pin "2") (pinfunction "GND_2") (pintype "passive"))
      (node (ref "IC5") (pin "3") (pinfunction "GND_3") (pintype "passive"))
      (node (ref "IC5") (pin "6") (pinfunction "GND_6") (pintype "passive"))
      (node (ref "IC5") (pin "7") (pinfunction "GND_7") (pintype "passive"))
      (node (ref "IC6") (pin "5") (pinfunction "GND_5") (pintype "passive"))
      (node (ref "IC7") (pin "15") (pinfunction "GND2_15") (pintype "passive"))
      (node (ref "IC7") (pin "9") (pinfunction "GND2_2_9") (pintype "passive"))
      (node (ref "Q10") (pin "2") (pinfunction "S_2") (pintype "passive"))
      (node (ref "Q11") (pin "2") (pinfunction "S_2") (pintype "passive"))
      (node (ref "Q16") (pin "2") (pinfunction "S_2") (pintype "passive"))
      (node (ref "Q18") (pin "2") (pinfunction "S_2") (pintype "passive"))
      (node (ref "Q20") (pin "E") (pinfunction "E_E") (pintype "passive"))
      (node (ref "Q21") (pin "2") (pinfunction "S_2") (pintype "passive"))
      (node (ref "Q23") (pin "E") (pinfunction "E_E") (pintype "passive"))
      (node (ref "Q25") (pin "2") (pinfunction "S_2") (pintype "passive"))
      (node (ref "R104") (pin "1") (pinfunction "1_1") (pintype "passive"))
      (node (ref "R112") (pin "1") (pinfunction "1_1") (pintype "passive"))
      (node (ref "R115") (pin "1") (pinfunction "1_1") (pintype "passive"))
      (node (ref "R15") (pin "1") (pinfunction "1_1") (pintype "passive"))
      (node (ref "R16") (pin "1") (pinfunction "1_1") (pintype "passive"))
      (node (ref "R19") (pin "1") (pinfunction "1_1") (pintype "passive"))
      (node (ref "R21") (pin "1") (pinfunction "1_1") (pintype "passive"))
      (node (ref "R38") (pin "2") (pinfunction "2_2") (pintype "passive"))
      (node (ref "R55") (pin "1") (pinfunction "1_1") (pintype "passive"))
      (node (ref "R60") (pin "1") (pinfunction "1_1") (pintype "passive"))
      (node (ref "R66") (pin "1") (pinfunction "1_1") (pintype "passive"))
      (node (ref "R73") (pin "2") (pinfunction "2_2") (pintype "passive"))
      (node (ref "R79") (pin "1") (pinfunction "1_1") (pintype "passive"))
      (node (ref "R83") (pin "1") (pinfunction "1_1") (pintype "passive"))
      (node (ref "R92") (pin "2") (pinfunction "2_2") (pintype "passive"))
      (node (ref "R97") (pin "1") (pinfunction "1_1") (pintype "passive"))
      (node (ref "R98") (pin "1") (pinfunction "1_1") (pintype "passive"))
      (node (ref "SH1") (pin "2") (pinfunction "GND_B_2") (pintype "bidirectional"))
      (node (ref "TR1") (pin "4") (pinfunction "4_4") (pintype "passive"))
      (node (ref "X3") (pin "2") (pinfunction "1_2") (pintype "passive"))
      (node (ref "ZD3") (pin "1") (pinfunction "A_1") (pintype "passive"))
      (node (ref "ZD3") (pin "2") (pinfunction "A_2") (pintype "passive"))
    )
    (net (code "35") (name "GNDIO") (class "Default")
      (node (ref "C33") (pin "2") (pinfunction "2_2") (pintype "passive"))
      (node (ref "C38") (pin "2") (pinfunction "2_2") (pintype "passive"))
      (node (ref "C41") (pin "1") (pinfunction "1_1") (pintype "passive"))
      (node (ref "IC3") (pin "2") (pinfunction "GND1_2_2") (pintype "passive"))
      (node (ref "IC3") (pin "8") (pinfunction "GND1_8") (pintype "passive"))
      (node (ref "IC7") (pin "2") (pinfunction "GND1_2_2") (pintype "passive"))
      (node (ref "IC7") (pin "5") (pinfunction "A3_5") (pintype "input"))
      (node (ref "IC7") (pin "8") (pinfunction "GND1_8") (pintype "passive"))
      (node (ref "IC8") (pin "4") (pinfunction "GND_4") (pintype "passive"))
      (node (ref "IC8") (pin "7") (pinfunction "WP_7") (pintype "input"))
      (node (ref "X2") (pin "11") (pinfunction "1_11") (pintype "passive"))
      (node (ref "X2") (pin "16") (pinfunction "1_16") (pintype "passive"))
      (node (ref "X2") (pin "20") (pinfunction "1_20") (pintype "passive"))
      (node (ref "X2") (pin "7") (pinfunction "1_7") (pintype "passive"))
    )
    (net (code "36") (name "HO") (class "Default")
      (node (ref "IC1") (pin "18") (pinfunction "HO_18") (pintype "output"))
      (node (ref "Q1") (pin "4") (pinfunction "G_4") (pintype "passive"))
    )
    (net (code "37") (name "IRQ") (class "Default")
      (node (ref "IC14") (pin "20") (pinfunction "INTA_20") (pintype "output"))
      (node (ref "IC7") (pin "11") (pinfunction "B4_11") (pintype "input"))
    )
    (net (code "38") (name "ISENSE+") (class "Default")
      (node (ref "IC11") (pin "3") (pinfunction "+IN_3") (pintype "input"))
      (node (ref "R58") (pin "2") (pinfunction "2_2") (pintype "passive"))
      (node (ref "R59") (pin "2") (pinfunction "2_2") (pintype "passive"))
    )
    (net (code "39") (name "ISENSE-") (class "Default")
      (node (ref "IC11") (pin "2") (pinfunction "-IN_2") (pintype "input"))
      (node (ref "R65") (pin "1") (pinfunction "1_1") (pintype "passive"))
      (node (ref "R68") (pin "2") (pinfunction "2_2") (pintype "passive"))
    )
    (net (code "40") (name "I_MON") (class "Default")
      (node (ref "IC11") (pin "6") (pinfunction "OUT_6") (pintype "output"))
      (node (ref "IC12") (pin "4") (pinfunction "COM_4") (pintype "bidirectional"))
      (node (ref "R62") (pin "1") (pinfunction "1_1") (pintype "passive"))
      (node (ref "R65") (pin "2") (pinfunction "2_2") (pintype "passive"))
      (node (ref "R81") (pin "1") (pinfunction "1_1") (pintype "passive"))
    )
    (net (code "41") (name "I_SERVO") (class "Default")
      (node (ref "C55") (pin "2") (pinfunction "2_2") (pintype "passive"))
      (node (ref "C61") (pin "2") (pinfunction "2_2") (pintype "passive"))
      (node (ref "D13") (pin "C") (pinfunction "C_C") (pintype "passive"))
      (node (ref "IC10") (pin "1") (pinfunction "OUT_1") (pintype "output"))
      (node (ref "R99") (pin "1") (pinfunction "1_1") (pintype "passive"))
    )
    (net (code "42") (name "I_SET") (class "Default")
      (node (ref "IC17") (pin "4") (pinfunction "VOUTA_4") (pintype "output"))
      (node (ref "R57") (pin "1") (pinfunction "1_1") (pintype "passive"))
      (node (ref "R77") (pin "1") (pinfunction "1_1") (pintype "passive"))
    )
    (net (code "43") (name "LO") (class "Default")
      (node (ref "IC1") (pin "13") (pinfunction "LO_13") (pintype "output"))
      (node (ref "Q2") (pin "4") (pinfunction "G_4") (pintype "passive"))
    )
    (net (code "44") (name "LOOP_CTRL") (class "Default")
      (node (ref "D11") (pin "A") (pinfunction "A_A") (pintype "passive"))
      (node (ref "D13") (pin "A") (pinfunction "A_A") (pintype "passive"))
      (node (ref "R40") (pin "1") (pinfunction "1_1") (pintype "passive"))
      (node (ref "R43") (pin "1") (pinfunction "1_1") (pintype "passive"))
      (node (ref "R93") (pin "2") (pinfunction "2_2") (pintype "passive"))
    )
    (net (code "45") (name "MISO") (class "Default")
      (node (ref "IC14") (pin "14") (pinfunction "SO_14") (pintype "output"))
      (node (ref "IC16") (pin "4") (pinfunction "SI/O_4") (pintype "bidirectional"))
      (node (ref "IC19") (pin "15") (pinfunction "DOUT/~{DRDY}_15") (pintype "output"))
      (node (ref "RN3") (pin "7") (pinfunction "2_7") (pintype "passive"))
    )
    (net (code "46") (name "MOSI") (class "Default")
      (node (ref "IC14") (pin "13") (pinfunction "SI_13") (pintype "input"))
      (node (ref "IC17") (pin "7") (pinfunction "DIN_7") (pintype "input"))
      (node (ref "IC19") (pin "16") (pinfunction "DIN_16") (pintype "input"))
      (node (ref "RN3") (pin "6") (pinfunction "2_6") (pintype "passive"))
    )
    (net (code "47") (name "Net-(C11-Pad2)") (class "Default")
      (node (ref "C11") (pin "2") (pinfunction "2_2") (pintype "passive"))
      (node (ref "R5") (pin "2") (pinfunction "2_2") (pintype "passive"))
    )
    (net (code "48") (name "Net-(C13-Pad1)") (class "Default")
      (node (ref "C13") (pin "1") (pinfunction "1_1") (pintype "passive"))
      (node (ref "C14") (pin "1") (pinfunction "1_1") (pintype "passive"))
      (node (ref "C15") (pin "+") (pinfunction "+_+") (pintype "passive"))
      (node (ref "C17") (pin "1") (pinfunction "1_1") (pintype "passive"))
      (node (ref "L2") (pin "2") (pinfunction "2_2") (pintype "passive"))
      (node (ref "L3") (pin "1") (pinfunction "1_1") (pintype "passive"))
      (node (ref "R2") (pin "2") (pinfunction "2_2") (pintype "passive"))
      (node (ref "R7") (pin "1") (pinfunction "1_1") (pintype "passive"))
      (node (ref "R8") (pin "1") (pinfunction "1_1") (pintype "passive"))
    )
    (net (code "49") (name "Net-(C19-Pad1)") (class "Default")
      (node (ref "C19") (pin "1") (pinfunction "1_1") (pintype "passive"))
      (node (ref "R6") (pin "1") (pinfunction "1_1") (pintype "passive"))
    )
    (net (code "50") (name "Net-(C22-Pad2)") (class "Default")
      (node (ref "C22") (pin "2") (pinfunction "2_2") (pintype "passive"))
      (node (ref "D3") (pin "A") (pinfunction "A_A") (pintype "passive"))
      (node (ref "Q3") (pin "B") (pinfunction "B_B") (pintype "passive"))
      (node (ref "R10") (pin "1") (pinfunction "1_1") (pintype "passive"))
      (node (ref "R8") (pin "2") (pinfunction "2_2") (pintype "passive"))
    )
    (net (code "51") (name "Net-(C23-Pad1)") (class "Default")
      (node (ref "C23") (pin "1") (pinfunction "1_1") (pintype "passive"))
      (node (ref "D4") (pin "A") (pinfunction "A_A") (pintype "passive"))
      (node (ref "R12") (pin "2") (pinfunction "2_2") (pintype "passive"))
    )
    (net (code "52") (name "Net-(C28-Pad2)") (class "Default")
      (node (ref "C28") (pin "2") (pinfunction "2_2") (pintype "passive"))
      (node (ref "R15") (pin "2") (pinfunction "2_2") (pintype "passive"))
    )
    (net (code "53") (name "Net-(C29-Pad1)") (class "Default")
      (node (ref "C29") (pin "1") (pinfunction "1_1") (pintype "passive"))
      (node (ref "R14") (pin "2") (pinfunction "2_2") (pintype "passive"))
      (node (ref "R18") (pin "2") (pinfunction "2_2") (pintype "passive"))
      (node (ref "TR1") (pin "3") (pinfunction "3_3") (pintype "passive"))
    )
    (net (code "54") (name "Net-(C36-Pad2)") (class "Default")
      (node (ref "C36") (pin "2") (pinfunction "2_2") (pintype "passive"))
      (node (ref "R20") (pin "1") (pinfunction "1_1") (pintype "passive"))
    )
    (net (code "55") (name "Net-(C43-Pad2)") (class "Default")
      (node (ref "C43") (pin "2") (pinfunction "2_2") (pintype "passive"))
      (node (ref "R41") (pin "1") (pinfunction "1_1") (pintype "passive"))
    )
    (net (code "56") (name "Net-(C44-Pad1)") (class "Default")
      (node (ref "C44") (pin "1") (pinfunction "1_1") (pintype "passive"))
      (node (ref "R44") (pin "1") (pinfunction "1_1") (pintype "passive"))
      (node (ref "R45") (pin "2") (pinfunction "2_2") (pintype "passive"))
      (node (ref "R46") (pin "2") (pinfunction "2_2") (pintype "passive"))
    )
    (net (code "57") (name "Net-(C46-Pad1)") (class "Default")
      (node (ref "C46") (pin "1") (pinfunction "1_1") (pintype "passive"))
      (node (ref "R51") (pin "2") (pinfunction "2_2") (pintype "passive"))
    )
    (net (code "58") (name "Net-(C47-Pad2)") (class "Default")
      (node (ref "C47") (pin "2") (pinfunction "2_2") (pintype "passive"))
      (node (ref "R53") (pin "1") (pinfunction "1_1") (pintype "passive"))
    )
    (net (code "59") (name "Net-(C48-Pad1)") (class "Default")
      (node (ref "C48") (pin "1") (pinfunction "1_1") (pintype "passive"))
      (node (ref "R56") (pin "1") (pinfunction "1_1") (pintype "passive"))
      (node (ref "R57") (pin "2") (pinfunction "2_2") (pintype "passive"))
    )
    (net (code "60") (name "Net-(C55-Pad1)") (class "Default")
      (node (ref "C55") (pin "1") (pinfunction "1_1") (pintype "passive"))
      (node (ref "R63") (pin "1") (pinfunction "1_1") (pintype "passive"))
    )
    (net (code "61") (name "Net-(C62-Pad2)") (class "Default")
      (node (ref "C62") (pin "2") (pinfunction "2_2") (pintype "passive"))
      (node (ref "R69") (pin "1") (pinfunction "1_1") (pintype "passive"))
    )
    (net (code "62") (name "Net-(C88-Pad2)") (class "Default")
      (node (ref "C88") (pin "2") (pinfunction "2_2") (pintype "passive"))
      (node (ref "Q22") (pin "B") (pinfunction "B_B") (pintype "passive"))
      (node (ref "R105") (pin "1") (pinfunction "1_1") (pintype "passive"))
      (node (ref "R106") (pin "2") (pinfunction "2_2") (pintype "passive"))
      (node (ref "R107") (pin "2") (pinfunction "2_2") (pintype "passive"))
    )
    (net (code "63") (name "Net-(C89-Pad2)") (class "Default")
      (node (ref "C89") (pin "2") (pinfunction "2_2") (pintype "passive"))
      (node (ref "R110") (pin "2") (pinfunction "2_2") (pintype "passive"))
    )
    (net (code "64") (name "Net-(C93-Pad1)") (class "Default")
      (node (ref "C93") (pin "1") (pinfunction "1_1") (pintype "passive"))
      (node (ref "Q24") (pin "B") (pinfunction "B_B") (pintype "passive"))
      (node (ref "R111") (pin "1") (pinfunction "1_1") (pintype "passive"))
      (node (ref "R113") (pin "2") (pinfunction "2_2") (pintype "passive"))
    )
    (net (code "65") (name "Net-(D3-PadC)") (class "Default")
      (node (ref "D3") (pin "C") (pinfunction "C_C") (pintype "passive"))
      (node (ref "Q3") (pin "E") (pinfunction "E_E") (pintype "passive"))
      (node (ref "R7") (pin "2") (pinfunction "2_2") (pintype "passive"))
    )
    (net (code "66") (name "Net-(D4-PadC)") (class "Default")
      (node (ref "D4") (pin "C") (pinfunction "C_C") (pintype "passive"))
      (node (ref "TR1") (pin "2") (pinfunction "2_2") (pintype "passive"))
    )
    (net (code "67") (name "Net-(D10-PadA)") (class "Default")
      (node (ref "D10") (pin "A") (pinfunction "A_A") (pintype "passive"))
      (node (ref "Q8") (pin "B") (pinfunction "B_B") (pintype "passive"))
      (node (ref "R39") (pin "2") (pinfunction "2_2") (pintype "passive"))
    )
    (net (code "68") (name "Net-(D17-PadA)") (class "Default")
      (node (ref "D17") (pin "A") (pinfunction "A_A") (pintype "passive"))
      (node (ref "Q17") (pin "B") (pinfunction "B_B") (pintype "passive"))
      (node (ref "R94") (pin "1") (pinfunction "1_1") (pintype "passive"))
      (node (ref "R97") (pin "2") (pinfunction "2_2") (pintype "passive"))
    )
    (net (code "69") (name "Net-(D17-PadC)") (class "Default")
      (node (ref "D17") (pin "C") (pinfunction "C_C") (pintype "passive"))
      (node (ref "D18") (pin "A") (pinfunction "A_A") (pintype "passive"))
    )
    (net (code "70") (name "Net-(FB1-1)") (class "Default")
      (node (ref "C37") (pin "1") (pinfunction "1_1") (pintype "passive"))
      (node (ref "D6") (pin "C") (pinfunction "C_C") (pintype "passive"))
      (node (ref "FB1") (pin "P$1") (pinfunction "1_P$1") (pintype "passive"))
      (node (ref "FB2") (pin "P$1") (pinfunction "1_P$1") (pintype "passive"))
      (node (ref "IC5") (pin "1") (pinfunction "VO_1") (pintype "passive"))
      (node (ref "TP2") (pin "1") (pinfunction "P$1_1") (pintype "bidirectional"))
    )
    (net (code "71") (name "Net-(FB3-1)") (class "Default")
      (node (ref "C40") (pin "2") (pinfunction "2_2") (pintype "passive"))
      (node (ref "D7") (pin "A") (pinfunction "A_A") (pintype "passive"))
      (node (ref "FB3") (pin "P$1") (pinfunction "1_P$1") (pintype "passive"))
      (node (ref "IC6") (pin "1") (pinfunction "OUT_1") (pintype "passive"))
      (node (ref "TP3") (pin "1") (pinfunction "P$1_1") (pintype "bidirectional"))
    )
    (net (code "72") (name "Net-(IC1-BST)") (class "Default")
      (node (ref "C8") (pin "1") (pinfunction "1_1") (pintype "passive"))
      (node (ref "IC1") (pin "17") (pinfunction "BST_17") (pintype "passive"))
    )
    (net (code "73") (name "Net-(IC1-COMP)") (class "Default")
      (node (ref "C19") (pin "2") (pinfunction "2_2") (pintype "passive"))
      (node (ref "C20") (pin "2") (pinfunction "2_2") (pintype "passive"))
      (node (ref "IC1") (pin "4") (pinfunction "COMP_4") (pintype "passive"))
    )
    (net (code "74") (name "Net-(IC1-EN_UVLO)") (class "Default")
      (node (ref "D1") (pin "C") (pinfunction "C_C") (pintype "passive"))
      (node (ref "IC1") (pin "1") (pinfunction "EN_UVLO_1") (pintype "input"))
      (node (ref "R3") (pin "2") (pinfunction "2_2") (pintype "passive"))
    )
    (net (code "75") (name "Net-(IC1-ILIM)") (class "Default")
      (node (ref "C12") (pin "1") (pinfunction "1_1") (pintype "passive"))
      (node (ref "IC1") (pin "11") (pinfunction "ILIM_11") (pintype "input"))
      (node (ref "R4") (pin "1") (pinfunction "1_1") (pintype "passive"))
    )
    (net (code "76") (name "Net-(IC1-RT)") (class "Default")
      (node (ref "IC1") (pin "2") (pinfunction "RT_2") (pintype "input"))
      (node (ref "R9") (pin "2") (pinfunction "2_2") (pintype "passive"))
    )
    (net (code "77") (name "Net-(IC1-SS_TRK)") (class "Default")
      (node (ref "C21") (pin "1") (pinfunction "1_1") (pintype "passive"))
      (node (ref "IC1") (pin "3") (pinfunction "SS_TRK_3") (pintype "input"))
    )
    (net (code "78") (name "Net-(IC1-SYNCIN)") (class "Default")
      (node (ref "IC1") (pin "8") (pinfunction "SYNCIN_8") (pintype "input"))
      (node (ref "JP1") (pin "2") (pinfunction "2_2") (pintype "passive"))
    )
    (net (code "79") (name "Net-(IC2-BOOT)") (class "Default")
      (node (ref "C27") (pin "2") (pinfunction "2_2") (pintype "passive"))
      (node (ref "IC2") (pin "1") (pinfunction "BOOT_1") (pintype "output"))
    )
    (net (code "80") (name "Net-(IC2-COMP)") (class "Default")
      (node (ref "C32") (pin "2") (pinfunction "2_2") (pintype "passive"))
      (node (ref "IC2") (pin "8") (pinfunction "COMP_8") (pintype "output"))
      (node (ref "R20") (pin "2") (pinfunction "2_2") (pintype "passive"))
    )
    (net (code "81") (name "Net-(IC2-EN)") (class "Default")
      (node (ref "IC2") (pin "3") (pinfunction "EN_3") (pintype "input"))
      (node (ref "R13") (pin "1") (pinfunction "1_1") (pintype "passive"))
      (node (ref "R16") (pin "2") (pinfunction "2_2") (pintype "passive"))
    )
    (net (code "82") (name "Net-(IC2-PH)") (class "Default")
      (node (ref "C27") (pin "1") (pinfunction "1_1") (pintype "passive"))
      (node (ref "C28") (pin "1") (pinfunction "1_1") (pintype "passive"))
      (node (ref "D5") (pin "C") (pinfunction "C_C") (pintype "passive"))
      (node (ref "IC2") (pin "10") (pinfunction "PH_10") (pintype "input"))
      (node (ref "TR1") (pin "1") (pinfunction "1_1") (pintype "passive"))
    )
    (net (code "83") (name "Net-(IC2-RT{slash}CLK)") (class "Default")
      (node (ref "IC2") (pin "5") (pinfunction "RT/CLK_5") (pintype "input"))
      (node (ref "R19") (pin "2") (pinfunction "2_2") (pintype "passive"))
    )
    (net (code "84") (name "Net-(IC2-SS{slash}TR)") (class "Default")
      (node (ref "C31") (pin "1") (pinfunction "1_1") (pintype "passive"))
      (node (ref "IC2") (pin "4") (pinfunction "SS/TR_4") (pintype "input"))
    )
    (net (code "85") (name "Net-(IC2-VSENSE)") (class "Default")
      (node (ref "IC2") (pin "7") (pinfunction "VSENSE_7") (pintype "input"))
      (node (ref "R18") (pin "1") (pinfunction "1_1") (pintype "passive"))
      (node (ref "R21") (pin "2") (pinfunction "2_2") (pintype "passive"))
    )
    (net (code "86") (name "Net-(IC3-B1)") (class "Default")
      (node (ref "IC3") (pin "14") (pinfunction "B1_14") (pintype "output"))
      (node (ref "RN3") (pin "1") (pinfunction "1_1") (pintype "passive"))
    )
    (net (code "87") (name "Net-(IC3-B4)") (class "Default")
      (node (ref "IC3") (pin "11") (pinfunction "B4_11") (pintype "input"))
      (node (ref "RN3") (pin "2") (pinfunction "1_2") (pintype "passive"))
    )
    (net (code "88") (name "Net-(IC4-Y0)") (class "Default")
      (node (ref "IC4") (pin "7") (pinfunction "Y0_7") (pintype "output"))
      (node (ref "RN2") (pin "1") (pinfunction "1_1") (pintype "passive"))
    )
    (net (code "89") (name "Net-(IC4-Y1)") (class "Default")
      (node (ref "IC4") (pin "6") (pinfunction "Y1_6") (pintype "output"))
      (node (ref "RN2") (pin "2") (pinfunction "1_2") (pintype "passive"))
    )
    (net (code "90") (name "Net-(IC4-Y2)") (class "Default")
      (node (ref "IC4") (pin "5") (pinfunction "Y2_5") (pintype "output"))
      (node (ref "RN2") (pin "3") (pinfunction "1_3") (pintype "passive"))
    )
    (net (code "91") (name "Net-(IC4-Y3)") (class "Default")
      (node (ref "IC4") (pin "3") (pinfunction "Y3_3") (pintype "output"))
      (node (ref "RN2") (pin "4") (pinfunction "1_4") (pintype "passive"))
    )
    (net (code "92") (name "Net-(IC7-B1)") (class "Default")
      (node (ref "IC7") (pin "14") (pinfunction "B1_14") (pintype "output"))
      (node (ref "RN3") (pin "3") (pinfunction "1_3") (pintype "passive"))
    )
    (net (code "93") (name "Net-(IC7-B2)") (class "Default")
      (node (ref "IC7") (pin "13") (pinfunction "B2_13") (pintype "output"))
      (node (ref "RN3") (pin "4") (pinfunction "1_4") (pintype "passive"))
    )
    (net (code "94") (name "Net-(IC9A-+IN)") (class "Default")
      (node (ref "IC9") (pin "3") (pinfunction "+IN_3") (pintype "input"))
      (node (ref "R41") (pin "2") (pinfunction "2_2") (pintype "passive"))
      (node (ref "R44") (pin "2") (pinfunction "2_2") (pintype "passive"))
    )
    (net (code "95") (name "Net-(IC9A--IN)") (class "Default")
      (node (ref "C45") (pin "1") (pinfunction "1_1") (pintype "passive"))
      (node (ref "IC9") (pin "2") (pinfunction "-IN_2") (pintype "input"))
      (node (ref "R51") (pin "1") (pinfunction "1_1") (pintype "passive"))
      (node (ref "R52") (pin "2") (pinfunction "2_2") (pintype "passive"))
      (node (ref "R53") (pin "2") (pinfunction "2_2") (pintype "passive"))
    )
    (net (code "96") (name "Net-(IC9B-+IN)") (class "Default")
      (node (ref "IC9") (pin "5") (pinfunction "+IN_5") (pintype "input"))
      (node (ref "R42") (pin "2") (pinfunction "2_2") (pintype "passive"))
      (node (ref "R47") (pin "1") (pinfunction "1_1") (pintype "passive"))
    )
    (net (code "97") (name "Net-(IC9B--IN)") (class "Default")
      (node (ref "IC9") (pin "6") (pinfunction "-IN_6") (pintype "input"))
      (node (ref "R48") (pin "1") (pinfunction "1_1") (pintype "passive"))
      (node (ref "R49") (pin "2") (pinfunction "2_2") (pintype "passive"))
    )
    (net (code "98") (name "Net-(IC10A-+IN)") (class "Default")
      (node (ref "IC10") (pin "3") (pinfunction "+IN_3") (pintype "input"))
      (node (ref "R56") (pin "2") (pinfunction "2_2") (pintype "passive"))
    )
    (net (code "99") (name "Net-(IC10A--IN)") (class "Default")
      (node (ref "C61") (pin "1") (pinfunction "1_1") (pintype "passive"))
      (node (ref "IC10") (pin "2") (pinfunction "-IN_2") (pintype "input"))
      (node (ref "R62") (pin "2") (pinfunction "2_2") (pintype "passive"))
      (node (ref "R63") (pin "2") (pinfunction "2_2") (pintype "passive"))
      (node (ref "R64") (pin "2") (pinfunction "2_2") (pintype "passive"))
      (node (ref "R69") (pin "2") (pinfunction "2_2") (pintype "passive"))
    )
    (net (code "100") (name "Net-(IC10B-+IN)") (class "Default")
      (node (ref "C42") (pin "1") (pinfunction "1_1") (pintype "passive"))
      (node (ref "IC10") (pin "5") (pinfunction "+IN_5") (pintype "input"))
      (node (ref "R31") (pin "2") (pinfunction "2_2") (pintype "passive"))
      (node (ref "R38") (pin "1") (pinfunction "1_1") (pintype "passive"))
    )
    (net (code "101") (name "Net-(IC12-NO)") (class "Default")
      (node (ref "IC12") (pin "1") (pinfunction "NO_1") (pintype "bidirectional"))
      (node (ref "R64") (pin "1") (pinfunction "1_1") (pintype "passive"))
    )
    (net (code "102") (name "Net-(IC13A-~{CLR})") (class "Default")
      (node (ref "D15") (pin "A") (pinfunction "A_A") (pintype "passive"))
      (node (ref "D16") (pin "A") (pinfunction "A_A") (pintype "passive"))
      (node (ref "IC13") (pin "6") (pinfunction "~{CLR}_6") (pintype "input"))
      (node (ref "R71") (pin "2") (pinfunction "2_2") (pintype "passive"))
    )
    (net (code "103") (name "Net-(IC14-~{RESET})") (class "Default")
      (node (ref "IC14") (pin "18") (pinfunction "~{RESET}_18") (pintype "input"))
      (node (ref "R70") (pin "2") (pinfunction "2_2") (pintype "passive"))
    )
    (net (code "104") (name "Net-(IC15-TRIM{slash}NR)") (class "Default")
      (node (ref "C70") (pin "1") (pinfunction "1_1") (pintype "passive"))
      (node (ref "IC15") (pin "5") (pinfunction "TRIM/NR_5") (pintype "input"))
    )
    (net (code "105") (name "Net-(IC18-NO)") (class "Default")
      (node (ref "IC18") (pin "1") (pinfunction "NO_1") (pintype "bidirectional"))
      (node (ref "R75") (pin "1") (pinfunction "1_1") (pintype "passive"))
      (node (ref "ZD3") (pin "3") (pinfunction "C_3") (pintype "passive"))
    )
    (net (code "106") (name "Net-(IC19-AIN0{slash}REFP1)") (class "Default")
      (node (ref "C77") (pin "2") (pinfunction "2_2") (pintype "passive"))
      (node (ref "IC19") (pin "11") (pinfunction "AIN0/REFP1_11") (pintype "input"))
      (node (ref "R80") (pin "2") (pinfunction "2_2") (pintype "passive"))
    )
    (net (code "107") (name "Net-(IC19-AIN1)") (class "Default")
      (node (ref "C74") (pin "2") (pinfunction "2_2") (pintype "passive"))
      (node (ref "IC19") (pin "10") (pinfunction "AIN1_10") (pintype "input"))
      (node (ref "R77") (pin "2") (pinfunction "2_2") (pintype "passive"))
    )
    (net (code "108") (name "Net-(IC19-AIN2)") (class "Default")
      (node (ref "C75") (pin "2") (pinfunction "2_2") (pintype "passive"))
      (node (ref "IC19") (pin "7") (pinfunction "AIN2_7") (pintype "input"))
      (node (ref "R78") (pin "2") (pinfunction "2_2") (pintype "passive"))
    )
    (net (code "109") (name "Net-(IC19-AIN3{slash}REFN1)") (class "Default")
      (node (ref "C76") (pin "1") (pinfunction "1_1") (pintype "passive"))
      (node (ref "IC19") (pin "6") (pinfunction "AIN3/REFN1_6") (pintype "input"))
      (node (ref "R81") (pin "2") (pinfunction "2_2") (pintype "passive"))
    )
    (net (code "110") (name "Net-(IC19-AVDD)") (class "Default")
      (node (ref "C80") (pin "2") (pinfunction "2_2") (pintype "passive"))
      (node (ref "C81") (pin "2") (pinfunction "2_2") (pintype "passive"))
      (node (ref "IC19") (pin "12") (pinfunction "AVDD_12") (pintype "power_in"))
      (node (ref "R82") (pin "2") (pinfunction "2_2") (pintype "passive"))
    )
    (net (code "111") (name "Net-(IC20A-+IN)") (class "Default")
      (node (ref "IC20") (pin "3") (pinfunction "+IN_3") (pintype "input"))
      (node (ref "IC20") (pin "5") (pinfunction "+IN_5") (pintype "input"))
      (node (ref "R93") (pin "1") (pinfunction "1_1") (pintype "passive"))
    )
    (net (code "112") (name "Net-(IC20A--IN)") (class "Default")
      (node (ref "IC20") (pin "2") (pinfunction "-IN_2") (pintype "input"))
      (node (ref "R85") (pin "2") (pinfunction "2_2") (pintype "passive"))
    )
    (net (code "113") (name "Net-(IC20A-OUT)") (class "Default")
      (node (ref "IC20") (pin "1") (pinfunction "OUT_1") (pintype "output"))
      (node (ref "R86") (pin "1") (pinfunction "1_1") (pintype "passive"))
    )
    (net (code "114") (name "Net-(IC20B--IN)") (class "Default")
      (node (ref "IC20") (pin "6") (pinfunction "-IN_6") (pintype "input"))
      (node (ref "R99") (pin "2") (pinfunction "2_2") (pintype "passive"))
    )
    (net (code "115") (name "Net-(IC20B-OUT)") (class "Default")
      (node (ref "IC20") (pin "7") (pinfunction "OUT_7") (pintype "output"))
      (node (ref "R100") (pin "1") (pinfunction "1_1") (pintype "passive"))
    )
    (net (code "116") (name "Net-(IC21-+IN)") (class "Default")
      (node (ref "C84") (pin "1") (pinfunction "1_1") (pintype "passive"))
      (node (ref "IC21") (pin "2") (pinfunction "+IN_2") (pintype "input"))
      (node (ref "R88") (pin "2") (pinfunction "2_2") (pintype "passive"))
      (node (ref "R92") (pin "1") (pinfunction "1_1") (pintype "passive"))
    )
    (net (code "117") (name "Net-(IC21--IN)") (class "Default")
      (node (ref "C84") (pin "2") (pinfunction "2_2") (pintype "passive"))
      (node (ref "IC21") (pin "3") (pinfunction "-IN_3") (pintype "input"))
      (node (ref "R95") (pin "2") (pinfunction "2_2") (pintype "passive"))
    )
    (net (code "118") (name "Net-(IC21-OUT)") (class "Default")
      (node (ref "IC21") (pin "7") (pinfunction "OUT_7") (pintype "output"))
      (node (ref "Q21") (pin "1") (pinfunction "G_1") (pintype "passive"))
      (node (ref "R101") (pin "2") (pinfunction "2_2") (pintype "passive"))
      (node (ref "R94") (pin "2") (pinfunction "2_2") (pintype "passive"))
    )
    (net (code "119") (name "Net-(IC21-~{SHDN})") (class "Default")
      (node (ref "IC21") (pin "6") (pinfunction "~{SHDN}_6") (pintype "input"))
      (node (ref "JP3") (pin "2") (pinfunction "2_2") (pintype "passive"))
    )
    (net (code "120") (name "Net-(K1A-NO)") (class "Default")
      (node (ref "K1") (pin "5") (pinfunction "NO_5") (pintype "passive"))
      (node (ref "X3") (pin "4") (pinfunction "1_4") (pintype "passive"))
    )
    (net (code "121") (name "Net-(K1B-NO)") (class "Default")
      (node (ref "K1") (pin "8") (pinfunction "NO_8") (pintype "passive"))
      (node (ref "X3") (pin "5") (pinfunction "1_5") (pintype "passive"))
    )
    (net (code "122") (name "Net-(K1C-C2)") (class "Default")
      (node (ref "D19") (pin "A") (pinfunction "A_A") (pintype "passive"))
      (node (ref "K1") (pin "12") (pinfunction "C2_12") (pintype "passive"))
      (node (ref "Q25") (pin "3") (pinfunction "D_3") (pintype "passive"))
      (node (ref "R114") (pin "1") (pinfunction "1_1") (pintype "passive"))
    )
    (net (code "123") (name "Net-(LED1-C)") (class "Default")
      (node (ref "LED1") (pin "CC") (pinfunction "C_CC") (pintype "passive"))
      (node (ref "R73") (pin "1") (pinfunction "1_1") (pintype "passive"))
    )
    (net (code "124") (name "Net-(LED2A-C)") (class "Default")
      (node (ref "LED2") (pin "BC") (pinfunction "C_BC") (pintype "passive"))
      (node (ref "R79") (pin "2") (pinfunction "2_2") (pintype "passive"))
    )
    (net (code "125") (name "Net-(LED2B-C)") (class "Default")
      (node (ref "LED2") (pin "TC") (pinfunction "C_TC") (pintype "passive"))
      (node (ref "R114") (pin "2") (pinfunction "2_2") (pintype "passive"))
    )
    (net (code "126") (name "Net-(LED3A-C)") (class "Default")
      (node (ref "LED3") (pin "BC") (pinfunction "C_BC") (pintype "passive"))
      (node (ref "R91") (pin "2") (pinfunction "2_2") (pintype "passive"))
    )
    (net (code "127") (name "Net-(LED3B-C)") (class "Default")
      (node (ref "LED3") (pin "TC") (pinfunction "C_TC") (pintype "passive"))
      (node (ref "R87") (pin "1") (pinfunction "1_1") (pintype "passive"))
    )
    (net (code "128") (name "Net-(Q4-B)") (class "Default")
      (node (ref "Q4") (pin "1") (pinfunction "B_1") (pintype "passive"))
      (node (ref "R33") (pin "2") (pinfunction "2_2") (pintype "passive"))
    )
    (net (code "129") (name "Net-(Q4-E)") (class "Default")
      (node (ref "Q4") (pin "3") (pinfunction "E_3") (pintype "passive"))
      (node (ref "R25") (pin "2") (pinfunction "2_2") (pintype "passive"))
    )
    (net (code "130") (name "Net-(Q5-B)") (class "Default")
      (node (ref "Q5") (pin "1") (pinfunction "B_1") (pintype "passive"))
      (node (ref "R34") (pin "2") (pinfunction "2_2") (pintype "passive"))
    )
    (net (code "131") (name "Net-(Q5-E)") (class "Default")
      (node (ref "Q5") (pin "3") (pinfunction "E_3") (pintype "passive"))
      (node (ref "R29") (pin "2") (pinfunction "2_2") (pintype "passive"))
    )
    (net (code "132") (name "Net-(Q6-G)") (class "Default")
      (node (ref "Q6") (pin "1") (pinfunction "G_1") (pintype "passive"))
      (node (ref "Q7") (pin "2") (pinfunction "C_2") (pintype "passive"))
      (node (ref "Q7") (pin "4") (pinfunction "C_4") (pintype "passive"))
      (node (ref "R27") (pin "2") (pinfunction "2_2") (pintype "passive"))
      (node (ref "ZD2") (pin "A") (pinfunction "A_A") (pintype "passive"))
    )
    (net (code "133") (name "Net-(Q6-S)") (class "Default")
      (node (ref "Q6") (pin "3") (pinfunction "S_3") (pintype "passive"))
      (node (ref "R26") (pin "1") (pinfunction "1_1") (pintype "passive"))
    )
    (net (code "134") (name "Net-(Q7-B)") (class "Default")
      (node (ref "Q7") (pin "1") (pinfunction "B_1") (pintype "passive"))
      (node (ref "R35") (pin "1") (pinfunction "1_1") (pintype "passive"))
      (node (ref "R36") (pin "1") (pinfunction "1_1") (pintype "passive"))
    )
    (net (code "135") (name "Net-(Q7-E)") (class "Default")
      (node (ref "Q7") (pin "3") (pinfunction "E_3") (pintype "passive"))
      (node (ref "R37") (pin "1") (pinfunction "1_1") (pintype "passive"))
    )
    (net (code "136") (name "Net-(Q8-PadC)") (class "Default")
      (node (ref "Q8") (pin "C") (pinfunction "C_C") (pintype "passive"))
      (node (ref "R35") (pin "2") (pinfunction "2_2") (pintype "passive"))
    )
    (net (code "137") (name "Net-(Q9-B)") (class "Default")
      (node (ref "D12") (pin "C") (pinfunction "C_C") (pintype "passive"))
      (node (ref "Q9") (pin "1") (pinfunction "B_1") (pintype "passive"))
      (node (ref "R43") (pin "2") (pinfunction "2_2") (pintype "passive"))
    )
    (net (code "138") (name "Net-(Q9-C-Pad2)") (class "Default")
      (node (ref "Q9") (pin "2") (pinfunction "C_2") (pintype "passive"))
      (node (ref "Q9") (pin "4") (pinfunction "C_4") (pintype "passive"))
      (node (ref "R32") (pin "1") (pinfunction "1_1") (pintype "passive"))
      (node (ref "R33") (pin "1") (pinfunction "1_1") (pintype "passive"))
      (node (ref "R34") (pin "1") (pinfunction "1_1") (pintype "passive"))
    )
    (net (code "139") (name "Net-(Q9-E)") (class "Default")
      (node (ref "D12") (pin "A") (pinfunction "A_A") (pintype "passive"))
      (node (ref "Q9") (pin "3") (pinfunction "E_3") (pintype "passive"))
      (node (ref "R50") (pin "2") (pinfunction "2_2") (pintype "passive"))
    )
    (net (code "140") (name "Net-(Q10-D)") (class "Default")
      (node (ref "Q10") (pin "3") (pinfunction "D_3") (pintype "passive"))
      (node (ref "R46") (pin "1") (pinfunction "1_1") (pintype "passive"))
    )
    (net (code "141") (name "Net-(Q11-D)") (class "Default")
      (node (ref "Q11") (pin "3") (pinfunction "D_3") (pintype "passive"))
      (node (ref "R50") (pin "1") (pinfunction "1_1") (pintype "passive"))
    )
    (net (code "142") (name "Net-(Q11-G)") (class "Default")
      (node (ref "Q11") (pin "1") (pinfunction "G_1") (pintype "passive"))
      (node (ref "R54") (pin "1") (pinfunction "1_1") (pintype "passive"))
      (node (ref "R55") (pin "2") (pinfunction "2_2") (pintype "passive"))
    )
    (net (code "143") (name "Net-(Q12-S-Pad1)") (class "Default")
      (node (ref "Q12") (pin "1") (pinfunction "S_1") (pintype "passive"))
      (node (ref "Q12") (pin "2") (pinfunction "S_2") (pintype "passive"))
      (node (ref "Q12") (pin "3") (pinfunction "S_3") (pintype "passive"))
      (node (ref "R59") (pin "1") (pinfunction "1_1") (pintype "passive"))
      (node (ref "R61") (pin "1") (pinfunction "1_1") (pintype "passive"))
    )
    (net (code "144") (name "Net-(Q13-S-Pad1)") (class "Default")
      (node (ref "Q13") (pin "1") (pinfunction "S_1") (pintype "passive"))
      (node (ref "Q13") (pin "2") (pinfunction "S_2") (pintype "passive"))
      (node (ref "Q13") (pin "3") (pinfunction "S_3") (pintype "passive"))
      (node (ref "R67") (pin "2") (pinfunction "2_2") (pintype "passive"))
    )
    (net (code "145") (name "Net-(Q14-D)") (class "Default")
      (node (ref "Q14") (pin "3") (pinfunction "D_3") (pintype "passive"))
      (node (ref "R74") (pin "2") (pinfunction "2_2") (pintype "passive"))
    )
    (net (code "146") (name "Net-(Q15-G)") (class "Default")
      (node (ref "Q15") (pin "3") (pinfunction "G_3") (pintype "passive"))
      (node (ref "Q17") (pin "C") (pinfunction "C_C") (pintype "passive"))
      (node (ref "R89") (pin "1") (pinfunction "1_1") (pintype "passive"))
      (node (ref "R90") (pin "1") (pinfunction "1_1") (pintype "passive"))
    )
    (net (code "147") (name "Net-(Q16-D)") (class "Default")
      (node (ref "Q16") (pin "3") (pinfunction "D_3") (pintype "passive"))
      (node (ref "R87") (pin "2") (pinfunction "2_2") (pintype "passive"))
    )
    (net (code "148") (name "Net-(Q17-PadE)") (class "Default")
      (node (ref "Q17") (pin "E") (pinfunction "E_E") (pintype "passive"))
      (node (ref "R98") (pin "2") (pinfunction "2_2") (pintype "passive"))
    )
    (net (code "149") (name "Net-(Q18-D)") (class "Default")
      (node (ref "Q18") (pin "3") (pinfunction "D_3") (pintype "passive"))
      (node (ref "R91") (pin "1") (pinfunction "1_1") (pintype "passive"))
    )
    (net (code "150") (name "Net-(Q19-G)") (class "Default")
      (node (ref "Q19") (pin "4") (pinfunction "G_4") (pintype "passive"))
      (node (ref "Q20") (pin "C") (pinfunction "C_C") (pintype "passive"))
      (node (ref "R101") (pin "1") (pinfunction "1_1") (pintype "passive"))
    )
    (net (code "151") (name "Net-(Q20-PadB)") (class "Default")
      (node (ref "Q20") (pin "B") (pinfunction "B_B") (pintype "passive"))
      (node (ref "R103") (pin "1") (pinfunction "1_1") (pintype "passive"))
      (node (ref "R104") (pin "2") (pinfunction "2_2") (pintype "passive"))
    )
    (net (code "152") (name "Net-(Q22-PadC)") (class "Default")
      (node (ref "Q22") (pin "C") (pinfunction "C_C") (pintype "passive"))
      (node (ref "R109") (pin "2") (pinfunction "2_2") (pintype "passive"))
    )
    (net (code "153") (name "Net-(Q23-PadB)") (class "Default")
      (node (ref "Q23") (pin "B") (pinfunction "B_B") (pintype "passive"))
      (node (ref "R109") (pin "1") (pinfunction "1_1") (pintype "passive"))
      (node (ref "R112") (pin "2") (pinfunction "2_2") (pintype "passive"))
    )
    (net (code "154") (name "Net-(Q24-PadC)") (class "Default")
      (node (ref "Q24") (pin "C") (pinfunction "C_C") (pintype "passive"))
      (node (ref "R107") (pin "1") (pinfunction "1_1") (pintype "passive"))
    )
    (net (code "155") (name "Net-(R28-Pad1)") (class "Default")
      (node (ref "R28") (pin "1") (pinfunction "1_1") (pintype "passive"))
      (node (ref "R30") (pin "2") (pinfunction "2_2") (pintype "passive"))
    )
    (net (code "156") (name "Net-(R61-Pad2)") (class "Default")
      (node (ref "R61") (pin "2") (pinfunction "2_2") (pintype "passive"))
      (node (ref "R67") (pin "2S") (pinfunction "2S_2S") (pintype "passive"))
    )
    (net (code "157") (name "Net-(R67-Pad1S)") (class "Default")
      (node (ref "R67") (pin "1S") (pinfunction "1S_1S") (pintype "passive"))
      (node (ref "R68") (pin "1") (pinfunction "1_1") (pintype "passive"))
    )
    (net (code "158") (name "Net-(R75-Pad2)") (class "Default")
      (node (ref "R75") (pin "2") (pinfunction "2_2") (pintype "passive"))
      (node (ref "R76") (pin "1") (pinfunction "1_1") (pintype "passive"))
    )
    (net (code "159") (name "Net-(R76-Pad2)") (class "Default")
      (node (ref "R76") (pin "2") (pinfunction "2_2") (pintype "passive"))
      (node (ref "X3") (pin "1") (pinfunction "1_1") (pintype "passive"))
    )
    (net (code "160") (name "Net-(R103-Pad2)") (class "Default")
      (node (ref "R103") (pin "2") (pinfunction "2_2") (pintype "passive"))
      (node (ref "ZD4") (pin "A") (pinfunction "A_A") (pintype "passive"))
    )
    (net (code "161") (name "Net-(RN1A-2)") (class "Default")
      (node (ref "RN1") (pin "8") (pinfunction "2_8") (pintype "passive"))
      (node (ref "X2") (pin "12") (pinfunction "1_12") (pintype "passive"))
    )
    (net (code "162") (name "Net-(RN1B-2)") (class "Default")
      (node (ref "RN1") (pin "7") (pinfunction "2_7") (pintype "passive"))
      (node (ref "X2") (pin "9") (pinfunction "1_9") (pintype "passive"))
    )
    (net (code "163") (name "Net-(RN1C-2)") (class "Default")
      (node (ref "RN1") (pin "6") (pinfunction "2_6") (pintype "passive"))
      (node (ref "X2") (pin "15") (pinfunction "1_15") (pintype "passive"))
    )
    (net (code "164") (name "Net-(RN1D-2)") (class "Default")
      (node (ref "RN1") (pin "5") (pinfunction "2_5") (pintype "passive"))
      (node (ref "X2") (pin "13") (pinfunction "1_13") (pintype "passive"))
    )
    (net (code "165") (name "Net-(X4B-1)") (class "Default")
      (node (ref "F2") (pin "2") (pinfunction "2_2") (pintype "passive"))
      (node (ref "X4") (pin "10") (pinfunction "1_10") (pintype "passive"))
      (node (ref "X4") (pin "6") (pinfunction "1_6") (pintype "passive"))
      (node (ref "X4") (pin "7") (pinfunction "1_7") (pintype "passive"))
      (node (ref "X4") (pin "8") (pinfunction "1_8") (pintype "passive"))
      (node (ref "X4") (pin "9") (pinfunction "1_9") (pintype "passive"))
    )
    (net (code "166") (name "OE") (class "Default")
      (node (ref "IC14") (pin "2") (pinfunction "GPB1_2") (pintype "bidirectional"))
      (node (ref "OE") (pin "1") (pinfunction "1_1") (pintype "passive"))
    )
    (net (code "167") (name "OE_GREEN") (class "Default")
      (node (ref "IC14") (pin "7") (pinfunction "GPB6_7") (pintype "bidirectional"))
      (node (ref "LED1") (pin "GREEN") (pinfunction "AG_GREEN") (pintype "passive"))
    )
    (net (code "168") (name "OE_RED") (class "Default")
      (node (ref "IC14") (pin "8") (pinfunction "GPB7_8") (pintype "bidirectional"))
      (node (ref "LED1") (pin "RED") (pinfunction "AR_RED") (pintype "passive"))
    )
    (net (code "169") (name "OE_SYNC") (class "Default")
      (node (ref "IC7") (pin "4") (pinfunction "A2_4") (pintype "input"))
      (node (ref "X2") (pin "6") (pinfunction "1_6") (pintype "passive"))
    )
    (net (code "170") (name "OE_TRIG") (class "Default")
      (node (ref "IC13") (pin "1") (pinfunction "CLK_1") (pintype "input"))
      (node (ref "RN3") (pin "5") (pinfunction "2_5") (pintype "passive"))
    )
    (net (code "171") (name "OUTC+") (class "Default")
      (node (ref "C91") (pin "1") (pinfunction "1_1") (pintype "passive"))
      (node (ref "J2") (pin "1") (pinfunction "1_1") (pintype "passive"))
      (node (ref "X4") (pin "1") (pinfunction "1_1") (pintype "passive"))
      (node (ref "X4") (pin "2") (pinfunction "1_2") (pintype "passive"))
      (node (ref "X4") (pin "3") (pinfunction "1_3") (pintype "passive"))
      (node (ref "X4") (pin "4") (pinfunction "1_4") (pintype "passive"))
      (node (ref "X4") (pin "5") (pinfunction "1_5") (pintype "passive"))
    )
    (net (code "172") (name "OUTC-") (class "Default")
      (node (ref "C92") (pin "2") (pinfunction "2_2") (pintype "passive"))
      (node (ref "J3") (pin "1") (pinfunction "1_1") (pintype "passive"))
      (node (ref "X4") (pin "16") (pinfunction "1_16") (pintype "passive"))
      (node (ref "X4") (pin "17") (pinfunction "1_17") (pintype "passive"))
      (node (ref "X4") (pin "18") (pinfunction "1_18") (pintype "passive"))
      (node (ref "X4") (pin "19") (pinfunction "1_19") (pintype "passive"))
      (node (ref "X4") (pin "20") (pinfunction "1_20") (pintype "passive"))
    )
    (net (code "173") (name "OVP_EN") (class "Default")
      (node (ref "IC14") (pin "5") (pinfunction "GPB4_5") (pintype "bidirectional"))
      (node (ref "JP3") (pin "1") (pinfunction "1_1") (pintype "passive"))
      (node (ref "R83") (pin "2") (pinfunction "2_2") (pintype "passive"))
    )
    (net (code "174") (name "PE") (class "Default")
      (node (ref "C2") (pin "2") (pinfunction "2_2") (pintype "passive"))
      (node (ref "C3") (pin "1") (pinfunction "1_1") (pintype "passive"))
      (node (ref "C91") (pin "2") (pinfunction "2_2") (pintype "passive"))
      (node (ref "C92") (pin "1") (pinfunction "1_1") (pintype "passive"))
      (node (ref "J1") (pin "1") (pinfunction "P$1_1") (pintype "bidirectional"))
      (node (ref "J1") (pin "2") (pinfunction "P$1_2") (pintype "bidirectional"))
      (node (ref "X3") (pin "3") (pinfunction "1_3") (pintype "passive"))
    )
    (net (code "175") (name "POST_OE") (class "Default")
      (node (ref "IC13") (pin "5") (pinfunction "Q_5") (pintype "output"))
      (node (ref "R54") (pin "2") (pinfunction "2_2") (pintype "passive"))
    )
    (net (code "176") (name "POST_OUT+") (class "Default")
      (node (ref "C47") (pin "1") (pinfunction "1_1") (pintype "passive"))
      (node (ref "C62") (pin "1") (pinfunction "1_1") (pintype "passive"))
      (node (ref "D8") (pin "A") (pinfunction "A_A") (pintype "passive"))
      (node (ref "F1") (pin "1") (pinfunction "1_1") (pintype "passive"))
      (node (ref "K1") (pin "3") (pinfunction "NC_3") (pintype "passive"))
      (node (ref "Q4") (pin "2") (pinfunction "C_2") (pintype "passive"))
      (node (ref "Q5") (pin "2") (pinfunction "C_2") (pintype "passive"))
      (node (ref "R10") (pin "2") (pinfunction "2_2") (pintype "passive"))
      (node (ref "R26") (pin "2") (pinfunction "2_2") (pintype "passive"))
      (node (ref "R27") (pin "1") (pinfunction "1_1") (pintype "passive"))
      (node (ref "R28") (pin "2") (pinfunction "2_2") (pintype "passive"))
      (node (ref "ZD2") (pin "C") (pinfunction "C_C") (pintype "passive"))
    )
    (net (code "177") (name "POST_OUT-") (class "Default")
      (node (ref "C43") (pin "1") (pinfunction "1_1") (pintype "passive"))
      (node (ref "C90") (pin "-") (pinfunction "-_-") (pintype "passive"))
      (node (ref "C93") (pin "2") (pinfunction "2_2") (pintype "passive"))
      (node (ref "D14") (pin "A") (pinfunction "A_A") (pintype "passive"))
      (node (ref "K1") (pin "10") (pinfunction "NC_10") (pintype "passive"))
      (node (ref "Q12") (pin "MB") (pinfunction "D_MB") (pintype "passive"))
      (node (ref "Q13") (pin "MB") (pinfunction "D_MB") (pintype "passive"))
      (node (ref "Q15") (pin "2") (pinfunction "A2_2") (pintype "passive"))
      (node (ref "Q19") (pin "1") (pinfunction "S_1") (pintype "passive"))
      (node (ref "Q19") (pin "2") (pinfunction "S_2") (pintype "passive"))
      (node (ref "Q19") (pin "3") (pinfunction "S_3") (pintype "passive"))
      (node (ref "Q24") (pin "E") (pinfunction "E_E") (pintype "passive"))
      (node (ref "R110") (pin "1") (pinfunction "1_1") (pintype "passive"))
      (node (ref "R113") (pin "1") (pinfunction "1_1") (pintype "passive"))
      (node (ref "X4") (pin "11") (pinfunction "1_11") (pintype "passive"))
      (node (ref "X4") (pin "12") (pinfunction "1_12") (pintype "passive"))
      (node (ref "X4") (pin "13") (pinfunction "1_13") (pintype "passive"))
      (node (ref "X4") (pin "14") (pinfunction "1_14") (pintype "passive"))
      (node (ref "X4") (pin "15") (pinfunction "1_15") (pintype "passive"))
      (node (ref "ZD5") (pin "A") (pinfunction "A_A") (pintype "passive"))
    )
    (net (code "178") (name "POST_OUTF+") (class "Default")
      (node (ref "C88") (pin "1") (pinfunction "1_1") (pintype "passive"))
      (node (ref "C89") (pin "1") (pinfunction "1_1") (pintype "passive"))
      (node (ref "C90") (pin "+") (pinfunction "+_+") (pintype "passive"))
      (node (ref "F1") (pin "2") (pinfunction "2_2") (pintype "passive"))
      (node (ref "F2") (pin "1") (pinfunction "1_1") (pintype "passive"))
      (node (ref "Q15") (pin "1") (pinfunction "A1_1") (pintype "passive"))
      (node (ref "Q19") (pin "MB") (pinfunction "D_MB") (pintype "passive"))
      (node (ref "Q22") (pin "E") (pinfunction "E_E") (pintype "passive"))
      (node (ref "R105") (pin "2") (pinfunction "2_2") (pintype "passive"))
      (node (ref "R89") (pin "2") (pinfunction "2_2") (pintype "passive"))
      (node (ref "R90") (pin "2") (pinfunction "2_2") (pintype "passive"))
      (node (ref "ZD4") (pin "C") (pinfunction "C_C") (pintype "passive"))
      (node (ref "ZD5") (pin "C") (pinfunction "C_C") (pintype "passive"))
    )
    (net (code "179") (name "PREG_OUT+") (class "Default")
      (node (ref "C16") (pin "+") (pinfunction "+_+") (pintype "passive"))
      (node (ref "C18") (pin "2") (pinfunction "2_2") (pintype "passive"))
      (node (ref "D8") (pin "C") (pinfunction "C_C") (pintype "passive"))
      (node (ref "L3") (pin "2") (pinfunction "2_2") (pintype "passive"))
      (node (ref "R2") (pin "1") (pinfunction "1_1") (pintype "passive"))
      (node (ref "R25") (pin "1") (pinfunction "1_1") (pintype "passive"))
      (node (ref "R29") (pin "1") (pinfunction "1_1") (pintype "passive"))
      (node (ref "R32") (pin "2") (pinfunction "2_2") (pintype "passive"))
      (node (ref "TP1") (pin "1") (pinfunction "P$1_1") (pintype "bidirectional"))
    )
    (net (code "180") (name "PREG_OUT-") (class "Default")
      (node (ref "C10") (pin "1") (pinfunction "1_1") (pintype "passive"))
      (node (ref "C12") (pin "2") (pinfunction "2_2") (pintype "passive"))
      (node (ref "C13") (pin "2") (pinfunction "2_2") (pintype "passive"))
      (node (ref "C14") (pin "2") (pinfunction "2_2") (pintype "passive"))
      (node (ref "C15") (pin "-") (pinfunction "-_-") (pintype "passive"))
      (node (ref "C16") (pin "-") (pinfunction "-_-") (pintype "passive"))
      (node (ref "C17") (pin "2") (pinfunction "2_2") (pintype "passive"))
      (node (ref "C18") (pin "1") (pinfunction "1_1") (pintype "passive"))
      (node (ref "C2") (pin "1") (pinfunction "1_1") (pintype "passive"))
      (node (ref "C4") (pin "-") (pinfunction "-_-") (pintype "passive"))
      (node (ref "C5") (pin "2") (pinfunction "2_2") (pintype "passive"))
      (node (ref "C6") (pin "2") (pinfunction "2_2") (pintype "passive"))
      (node (ref "C7") (pin "2") (pinfunction "2_2") (pintype "passive"))
      (node (ref "C7A") (pin "1") (pinfunction "1_1") (pintype "passive"))
      (node (ref "C9") (pin "1") (pinfunction "1_1") (pintype "passive"))
      (node (ref "D14") (pin "C") (pinfunction "C_C") (pintype "passive"))
      (node (ref "IC1") (pin "12") (pinfunction "PGND_12") (pintype "power_in"))
      (node (ref "IC1") (pin "15") (pinfunction "EP_15") (pintype "power_in"))
      (node (ref "IC1") (pin "21") (pinfunction "EP_21") (pintype "power_in"))
      (node (ref "L1") (pin "4") (pinfunction "2_4") (pintype "passive"))
      (node (ref "Q2") (pin "1") (pinfunction "S_1") (pintype "passive"))
      (node (ref "Q2") (pin "2") (pinfunction "S_2") (pintype "passive"))
      (node (ref "Q2") (pin "3") (pinfunction "S_3") (pintype "passive"))
      (node (ref "Q6") (pin "2") (pinfunction "D_2") (pintype "passive"))
      (node (ref "R30") (pin "1") (pinfunction "1_1") (pintype "passive"))
      (node (ref "R5") (pin "1") (pinfunction "1_1") (pintype "passive"))
      (node (ref "R67") (pin "1") (pinfunction "1_1") (pintype "passive"))
      (node (ref "SH1") (pin "1") (pinfunction "GND_A_1") (pintype "bidirectional"))
      (node (ref "SH2") (pin "2") (pinfunction "GND_B_2") (pintype "bidirectional"))
      (node (ref "ZD1") (pin "A") (pinfunction "A_A") (pintype "passive"))
    )
    (net (code "181") (name "PRE_OE") (class "Default")
      (node (ref "D1") (pin "A") (pinfunction "A_A") (pintype "passive"))
      (node (ref "IC13") (pin "2") (pinfunction "D_2") (pintype "input"))
      (node (ref "OE") (pin "2") (pinfunction "2_2") (pintype "passive"))
    )
    (net (code "182") (name "PWRGOOD") (class "Default")
      (node (ref "D15") (pin "C") (pinfunction "C_C") (pintype "passive"))
      (node (ref "IC14") (pin "24") (pinfunction "GPA3_24") (pintype "bidirectional"))
      (node (ref "IC2") (pin "6") (pinfunction "PWRGD_6") (pintype "output"))
      (node (ref "R17") (pin "2") (pinfunction "2_2") (pintype "passive"))
    )
    (net (code "183") (name "RSENSE") (class "Default")
      (node (ref "IC14") (pin "3") (pinfunction "GPB2_3") (pintype "bidirectional"))
      (node (ref "Q25") (pin "1") (pinfunction "G_1") (pintype "passive"))
      (node (ref "R115") (pin "2") (pinfunction "2_2") (pintype "passive"))
    )
    (net (code "184") (name "SCLK") (class "Default")
      (node (ref "IC14") (pin "12") (pinfunction "SCK_12") (pintype "input"))
      (node (ref "IC16") (pin "3") (pinfunction "SCLK_3") (pintype "input"))
      (node (ref "IC17") (pin "6") (pinfunction "SCLK_6") (pintype "input"))
      (node (ref "IC19") (pin "1") (pinfunction "SCLK_1") (pintype "input"))
      (node (ref "RN3") (pin "8") (pinfunction "2_8") (pintype "passive"))
    )
    (net (code "185") (name "SENSE+") (class "Default")
      (node (ref "K1") (pin "4") (pinfunction "COM_4") (pintype "passive"))
      (node (ref "R106") (pin "1") (pinfunction "1_1") (pintype "passive"))
      (node (ref "R47") (pin "2") (pinfunction "2_2") (pintype "passive"))
    )
    (net (code "186") (name "SENSE-") (class "Default")
      (node (ref "K1") (pin "9") (pinfunction "COM_9") (pintype "passive"))
      (node (ref "R111") (pin "2") (pinfunction "2_2") (pintype "passive"))
      (node (ref "R48") (pin "2") (pinfunction "2_2") (pintype "passive"))
    )
    (net (code "187") (name "SENSE_ERR") (class "Default")
      (node (ref "IC14") (pin "21") (pinfunction "GPA0_21") (pintype "bidirectional"))
      (node (ref "Q23") (pin "C") (pinfunction "C_C") (pintype "passive"))
      (node (ref "R108") (pin "1") (pinfunction "1_1") (pintype "passive"))
    )
    (net (code "188") (name "SW") (class "Default")
      (node (ref "C11") (pin "1") (pinfunction "1_1") (pintype "passive"))
      (node (ref "C8") (pin "2") (pinfunction "2_2") (pintype "passive"))
      (node (ref "IC1") (pin "19") (pinfunction "SW_19") (pintype "power_in"))
      (node (ref "L2") (pin "1") (pinfunction "1_1") (pintype "passive"))
      (node (ref "Q1") (pin "1") (pinfunction "S_1") (pintype "passive"))
      (node (ref "Q1") (pin "2") (pinfunction "S_2") (pintype "passive"))
      (node (ref "Q1") (pin "3") (pinfunction "S_3") (pintype "passive"))
      (node (ref "Q2") (pin "5") (pinfunction "D_5") (pintype "passive"))
      (node (ref "Q2") (pin "6") (pinfunction "D_6") (pintype "passive"))
      (node (ref "Q2") (pin "7") (pinfunction "D_7") (pintype "passive"))
      (node (ref "Q2") (pin "8") (pinfunction "D_8") (pintype "passive"))
      (node (ref "R4") (pin "2") (pinfunction "2_2") (pintype "passive"))
    )
    (net (code "189") (name "TEMP_CS") (class "Default")
      (node (ref "IC16") (pin "1") (pinfunction "~{CS}_1") (pintype "input"))
      (node (ref "RN2") (pin "5") (pinfunction "2_5") (pintype "passive"))
    )
    (net (code "190") (name "U_MON") (class "Default")
      (node (ref "IC9") (pin "7") (pinfunction "OUT_7") (pintype "output"))
      (node (ref "R49") (pin "1") (pinfunction "1_1") (pintype "passive"))
      (node (ref "R52") (pin "1") (pinfunction "1_1") (pintype "passive"))
      (node (ref "R80") (pin "1") (pinfunction "1_1") (pintype "passive"))
      (node (ref "R88") (pin "1") (pinfunction "1_1") (pintype "passive"))
    )
    (net (code "191") (name "U_SERVO") (class "Default")
      (node (ref "C45") (pin "2") (pinfunction "2_2") (pintype "passive"))
      (node (ref "C46") (pin "2") (pinfunction "2_2") (pintype "passive"))
      (node (ref "D11") (pin "C") (pinfunction "C_C") (pintype "passive"))
      (node (ref "IC9") (pin "1") (pinfunction "OUT_1") (pintype "output"))
      (node (ref "R39") (pin "1") (pinfunction "1_1") (pintype "passive"))
      (node (ref "R85") (pin "1") (pinfunction "1_1") (pintype "passive"))
    )
    (net (code "192") (name "U_SET") (class "Default")
      (node (ref "IC17") (pin "3") (pinfunction "VOUTB_3") (pintype "output"))
      (node (ref "IC18") (pin "3") (pinfunction "NC_3") (pintype "bidirectional"))
      (node (ref "R78") (pin "1") (pinfunction "1_1") (pintype "passive"))
    )
    (net (code "193") (name "U_SET_OUT") (class "Default")
      (node (ref "IC18") (pin "4") (pinfunction "COM_4") (pintype "bidirectional"))
      (node (ref "R45") (pin "1") (pinfunction "1_1") (pintype "passive"))
      (node (ref "R95") (pin "1") (pinfunction "1_1") (pintype "passive"))
    )
    (net (code "194") (name "V+") (class "Default")
      (node (ref "C49") (pin "2") (pinfunction "2_2") (pintype "passive"))
      (node (ref "C50") (pin "1") (pinfunction "1_1") (pintype "passive"))
      (node (ref "C51") (pin "2") (pinfunction "2_2") (pintype "passive"))
      (node (ref "C52") (pin "2") (pinfunction "2_2") (pintype "passive"))
      (node (ref "C53") (pin "2") (pinfunction "2_2") (pintype "passive"))
      (node (ref "C60") (pin "1") (pinfunction "1_1") (pintype "passive"))
      (node (ref "C66") (pin "1") (pinfunction "1_1") (pintype "passive"))
      (node (ref "C69") (pin "1") (pinfunction "1_1") (pintype "passive"))
      (node (ref "C71") (pin "2") (pinfunction "2_2") (pintype "passive"))
      (node (ref "C73") (pin "1") (pinfunction "1_1") (pintype "passive"))
      (node (ref "C83") (pin "2") (pinfunction "2_2") (pintype "passive"))
      (node (ref "C85") (pin "2") (pinfunction "2_2") (pintype "passive"))
      (node (ref "FB1") (pin "P$2") (pinfunction "2_P$2") (pintype "passive"))
      (node (ref "IC10") (pin "8") (pinfunction "V+_8") (pintype "power_in"))
      (node (ref "IC11") (pin "7") (pinfunction "V+_7") (pintype "power_in"))
      (node (ref "IC12") (pin "5") (pinfunction "VDD_5") (pintype "power_in"))
      (node (ref "IC15") (pin "2") (pinfunction "VIN_2") (pintype "passive"))
      (node (ref "IC17") (pin "1") (pinfunction "VDD_1") (pintype "power_in"))
      (node (ref "IC18") (pin "5") (pinfunction "VDD_5") (pintype "power_in"))
      (node (ref "IC20") (pin "8") (pinfunction "V+_8") (pintype "power_in"))
      (node (ref "IC21") (pin "1") (pinfunction "+VCC_1") (pintype "passive"))
      (node (ref "IC21") (pin "5") (pinfunction "~{LE}_5") (pintype "input"))
      (node (ref "IC9") (pin "8") (pinfunction "V+_8") (pintype "power_in"))
      (node (ref "R40") (pin "2") (pinfunction "2_2") (pintype "passive"))
      (node (ref "R82") (pin "1") (pinfunction "1_1") (pintype "passive"))
    )
    (net (code "195") (name "V-") (class "Default")
      (node (ref "C54") (pin "2") (pinfunction "2_2") (pintype "passive"))
      (node (ref "C56") (pin "2") (pinfunction "2_2") (pintype "passive"))
      (node (ref "C57") (pin "1") (pinfunction "1_1") (pintype "passive"))
      (node (ref "C58") (pin "2") (pinfunction "2_2") (pintype "passive"))
      (node (ref "C59") (pin "2") (pinfunction "2_2") (pintype "passive"))
      (node (ref "C87") (pin "2") (pinfunction "2_2") (pintype "passive"))
      (node (ref "FB3") (pin "P$2") (pinfunction "2_P$2") (pintype "passive"))
      (node (ref "IC10") (pin "4") (pinfunction "V-_4") (pintype "power_in"))
      (node (ref "IC11") (pin "4") (pinfunction "V-_4") (pintype "power_in"))
      (node (ref "IC20") (pin "4") (pinfunction "V-_4") (pintype "power_in"))
      (node (ref "IC9") (pin "4") (pinfunction "V-_4") (pintype "power_in"))
    )
    (net (code "196") (name "VCC") (class "Default")
      (node (ref "C10") (pin "2") (pinfunction "2_2") (pintype "passive"))
      (node (ref "D2") (pin "C") (pinfunction "C_C") (pintype "passive"))
      (node (ref "IC1") (pin "14") (pinfunction "VCC_14") (pintype "power_in"))
      (node (ref "JP1") (pin "1") (pinfunction "1_1") (pintype "passive"))
    )
    (net (code "197") (name "unconnected-(IC1-PGOOD-Pad10)") (class "Default")
      (node (ref "IC1") (pin "10") (pinfunction "PGOOD_10") (pintype "open_collector"))
    )
    (net (code "198") (name "unconnected-(IC1-SYNCOUT-Pad7)") (class "Default")
      (node (ref "IC1") (pin "7") (pinfunction "SYNCOUT_7") (pintype "output"))
    )
    (net (code "199") (name "unconnected-(IC7-B3-Pad12)") (class "Default")
      (node (ref "IC7") (pin "12") (pinfunction "B3_12") (pintype "output"))
    )
    (net (code "200") (name "unconnected-(IC12-NC-Pad3)") (class "Default")
      (node (ref "IC12") (pin "3") (pinfunction "NC_3") (pintype "bidirectional"))
    )
    (net (code "201") (name "unconnected-(IC13A-~{Q}-Pad3)") (class "Default")
      (node (ref "IC13") (pin "3") (pinfunction "~{Q}_3") (pintype "output"))
    )
    (net (code "202") (name "unconnected-(IC14-GPB5-Pad6)") (class "Default")
      (node (ref "IC14") (pin "6") (pinfunction "GPB5_6") (pintype "bidirectional"))
    )
    (net (code "203") (name "unconnected-(IC14-INTB-Pad19)") (class "Default")
      (node (ref "IC14") (pin "19") (pinfunction "INTB_19") (pintype "output"))
    )
    (net (code "204") (name "unconnected-(IC15-TEMP-Pad3)") (class "Default")
      (node (ref "IC15") (pin "3") (pinfunction "TEMP_3") (pintype "input"))
    )
    (net (code "205") (name "unconnected-(KK3-Pad1)") (class "Default")
      (node (ref "KK3") (pin "1") (pinfunction "1_1") (pintype "passive"))
    )
    (net (code "206") (name "unconnected-(KK3-Pad2)") (class "Default")
      (node (ref "KK3") (pin "2") (pinfunction "2_2") (pintype "passive"))
    )
    (net (code "207") (name "~{ADC_DRDY}") (class "Default")
      (node (ref "IC14") (pin "25") (pinfunction "GPA4_25") (pintype "bidirectional"))
      (node (ref "IC19") (pin "14") (pinfunction "~{DRDY}_14") (pintype "output"))
    )
    (net (code "208") (name "~{DP_DRIVE}") (class "Default")
      (node (ref "D9") (pin "A") (pinfunction "A_A") (pintype "passive"))
      (node (ref "Q8") (pin "E") (pinfunction "E_E") (pintype "passive"))
      (node (ref "R74") (pin "1") (pinfunction "1_1") (pintype "passive"))
    )
    (net (code "209") (name "~{OVP_FAULT}") (class "Default")
      (node (ref "C86") (pin "2") (pinfunction "2_2") (pintype "passive"))
      (node (ref "D16") (pin "C") (pinfunction "C_C") (pintype "passive"))
      (node (ref "IC14") (pin "26") (pinfunction "GPA5_26") (pintype "bidirectional"))
      (node (ref "Q21") (pin "3") (pinfunction "D_3") (pintype "passive"))
      (node (ref "R102") (pin "2") (pinfunction "2_2") (pintype "passive"))
    )
    (net (code "210") (name "~{SET_DP}") (class "Default")
      (node (ref "IC14") (pin "1") (pinfunction "GPB0_1") (pintype "bidirectional"))
      (node (ref "Q14") (pin "1") (pinfunction "G_1") (pintype "passive"))
      (node (ref "R72") (pin "2") (pinfunction "2_2") (pintype "passive"))
    )
  )
)
